# counterMeter.net
KiCad netlist of a schematic drawn in EAGLE
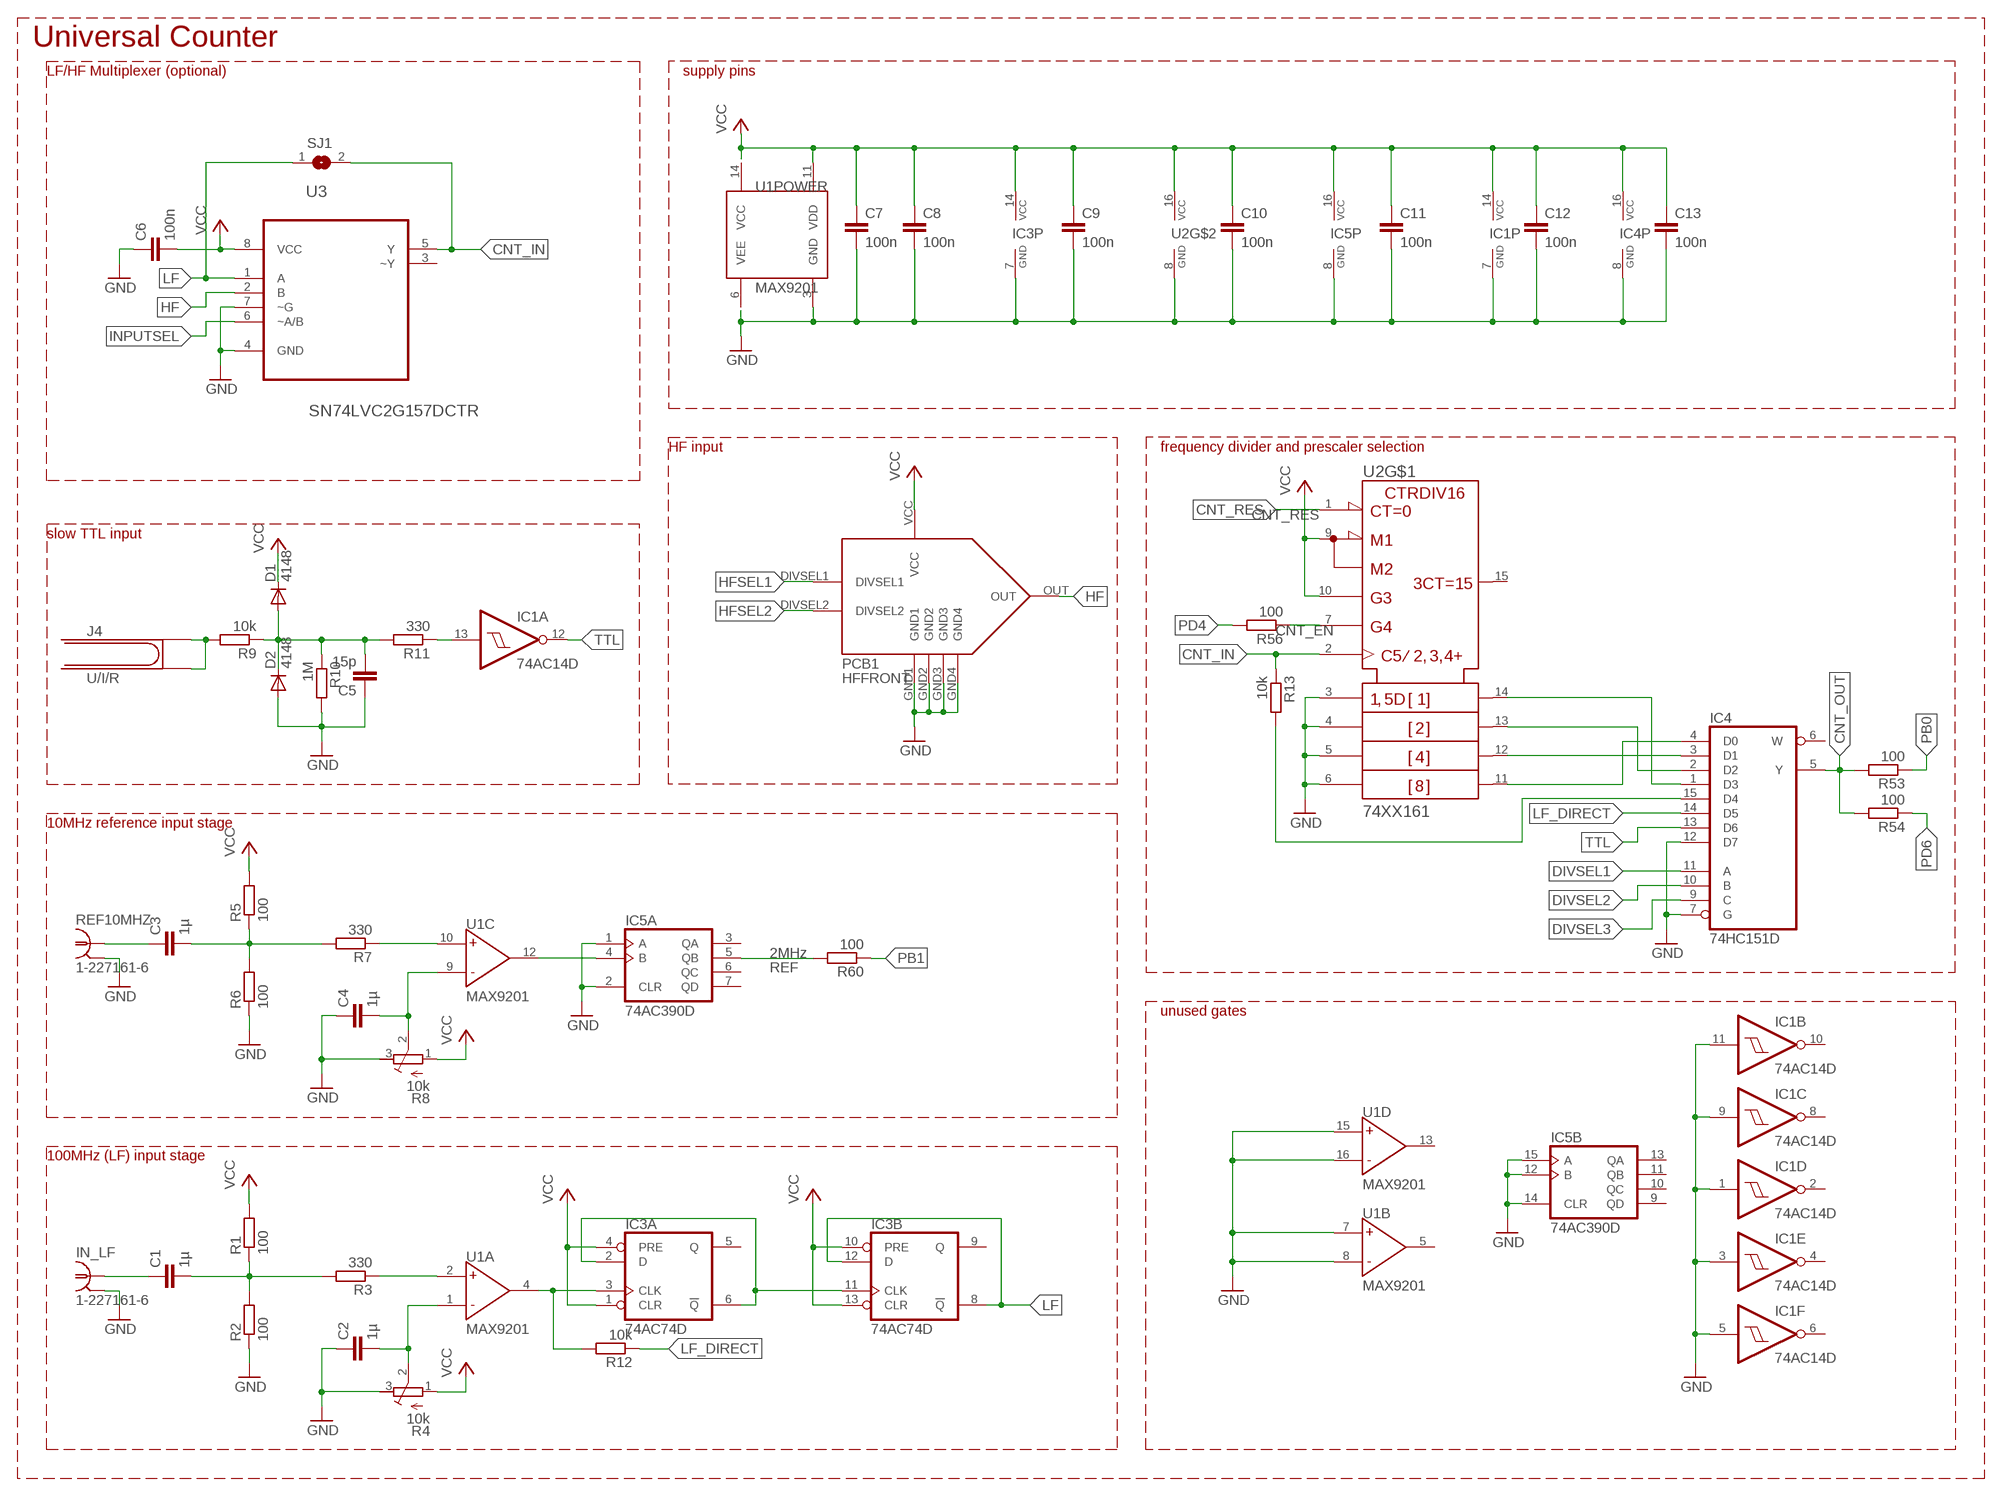
[diagram p0: schematic, sheet 1, part 1 of 2]
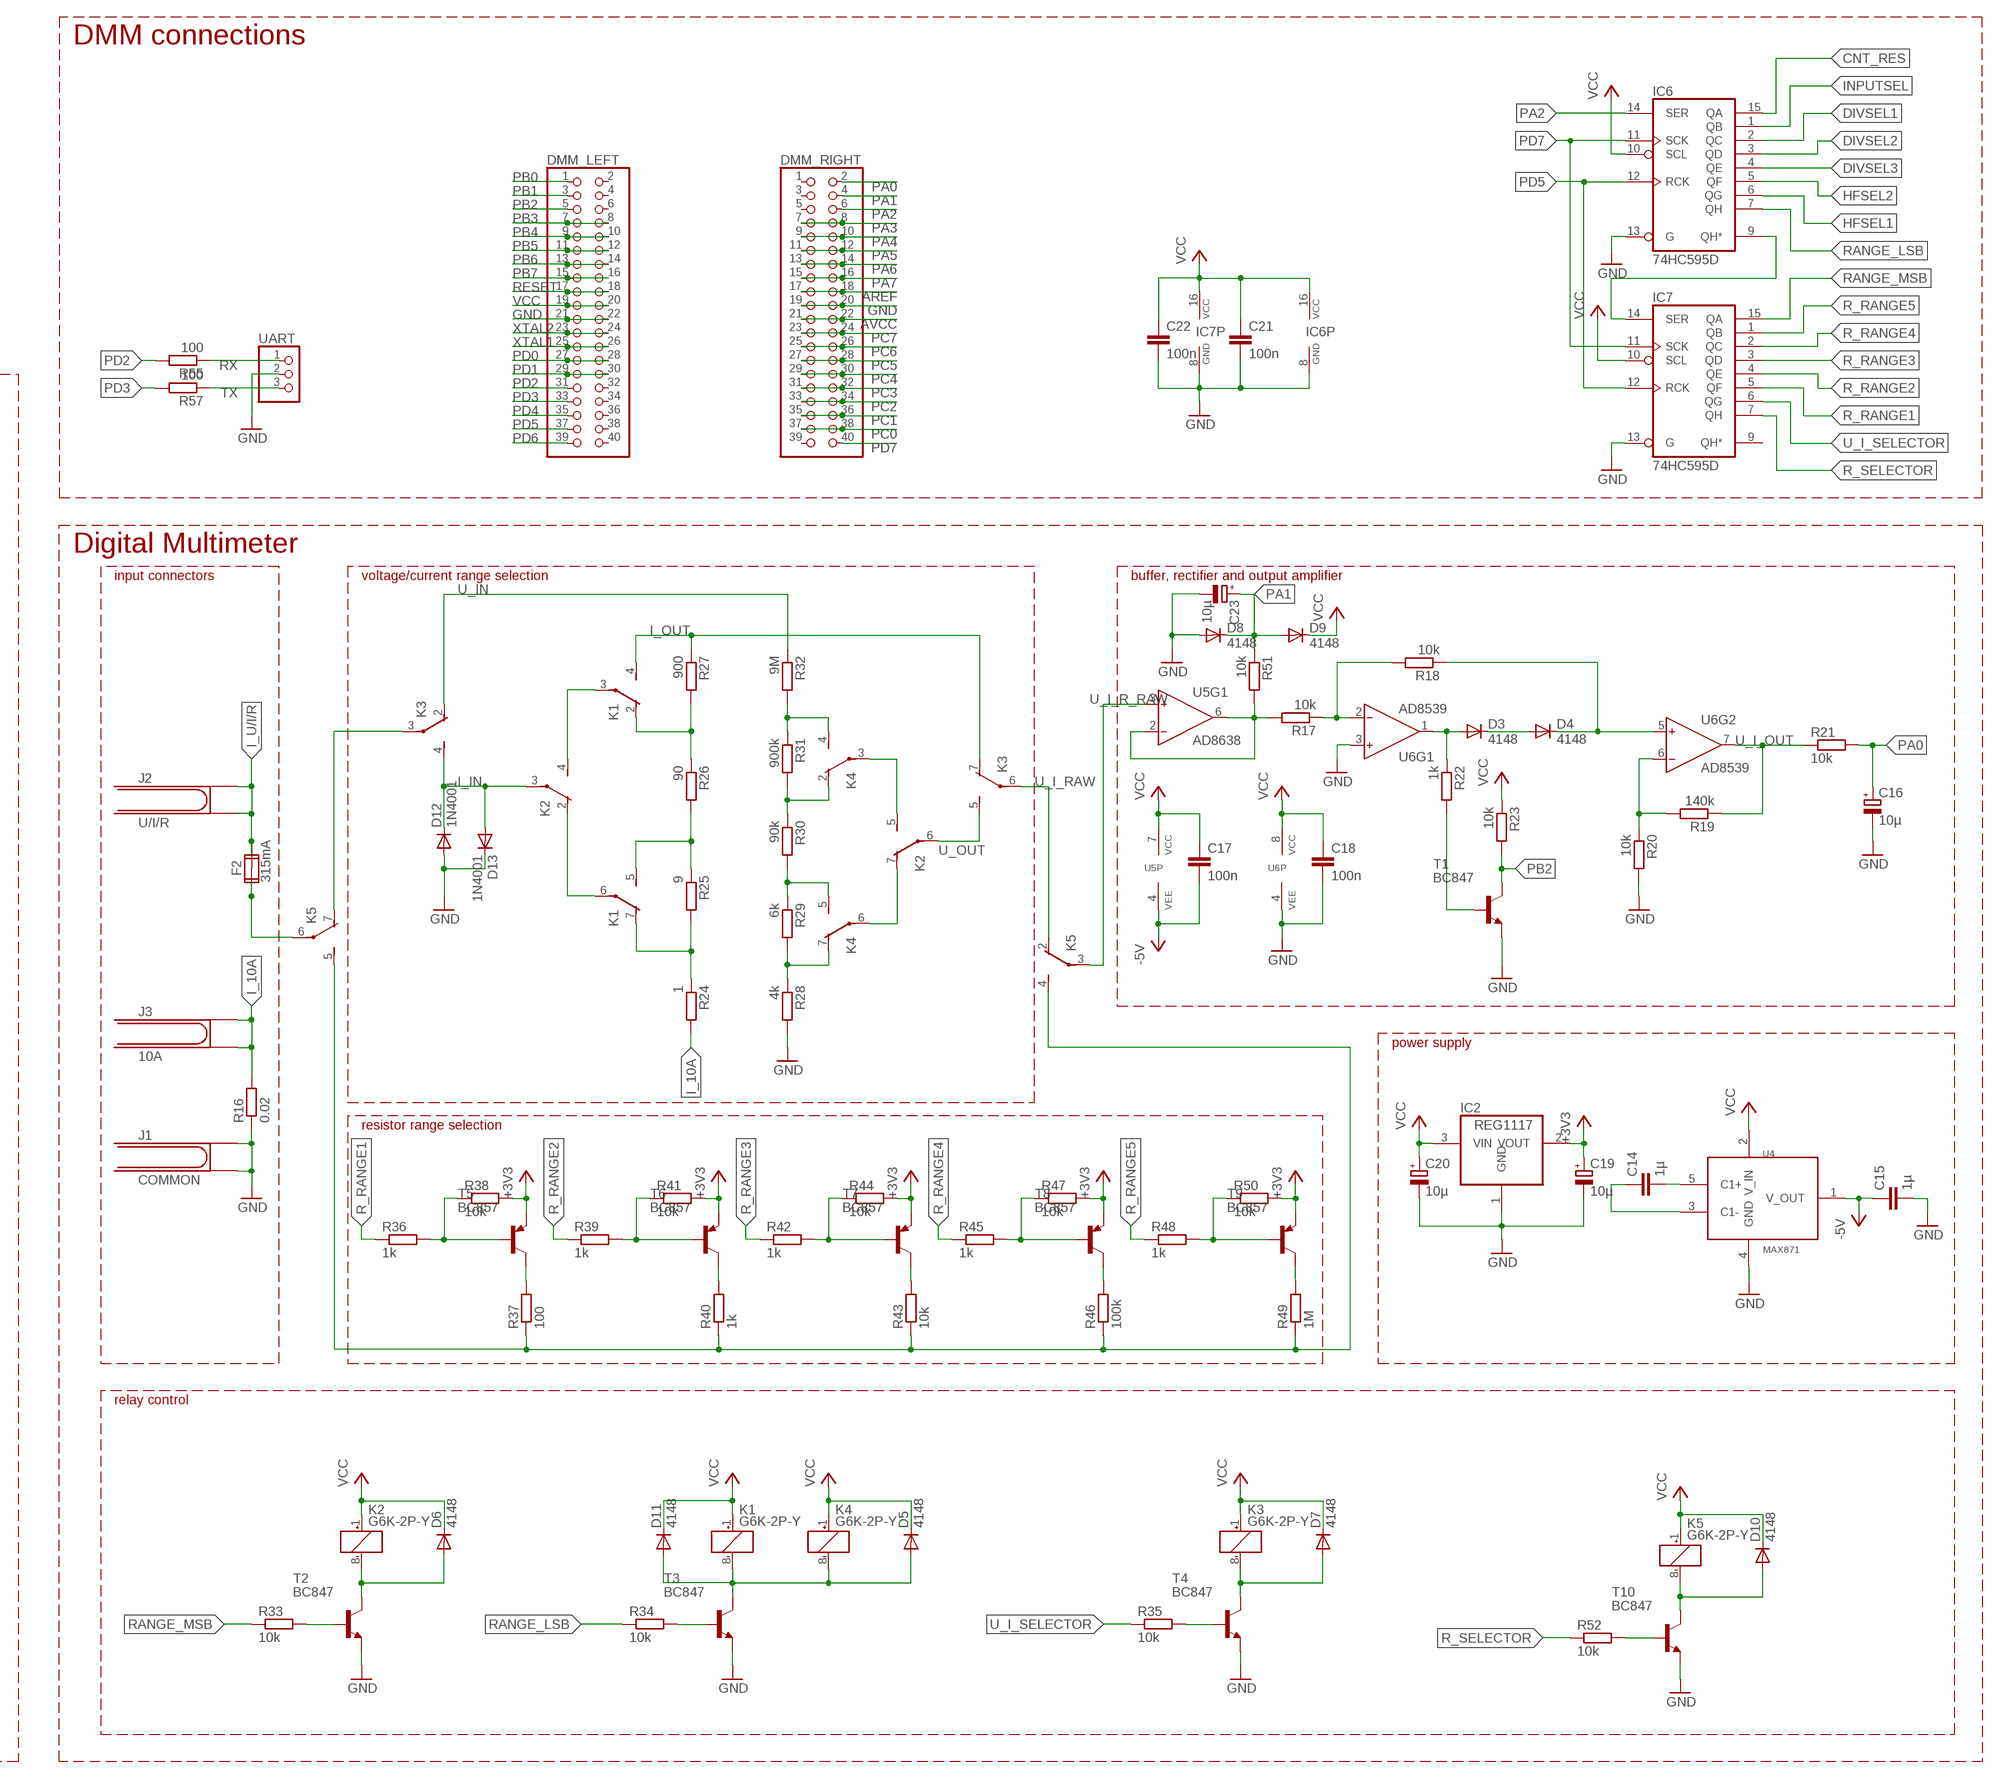
[diagram p1: schematic, sheet 1, part 2 of 2]

(export (version "E")
  (design (tool "Eeschema 10.0.6"))
  (components
    (comp (ref "C1")
      (value "1µ")
      (footprint "eagle-import:C0603")
      (libsource (lib "eagle-import") (part "C-EUC0603"))
    )
    (comp (ref "C2")
      (value "1µ")
      (footprint "eagle-import:C0603")
      (libsource (lib "eagle-import") (part "C-EUC0603"))
    )
    (comp (ref "C3")
      (value "1µ")
      (footprint "eagle-import:C0603")
      (libsource (lib "eagle-import") (part "C-EUC0603"))
    )
    (comp (ref "C4")
      (value "1µ")
      (footprint "eagle-import:C0603")
      (libsource (lib "eagle-import") (part "C-EUC0603"))
    )
    (comp (ref "C5")
      (value "15p")
      (footprint "eagle-import:C0603")
      (libsource (lib "eagle-import") (part "C-EUC0603"))
    )
    (comp (ref "C6")
      (value "100n")
      (footprint "eagle-import:C0603")
      (libsource (lib "eagle-import") (part "C-EUC0603"))
    )
    (comp (ref "C7")
      (value "100n")
      (footprint "eagle-import:C0603")
      (libsource (lib "eagle-import") (part "C-EUC0603"))
    )
    (comp (ref "C8")
      (value "100n")
      (footprint "eagle-import:C0603")
      (libsource (lib "eagle-import") (part "C-EUC0603"))
    )
    (comp (ref "C9")
      (value "100n")
      (footprint "eagle-import:C0603")
      (libsource (lib "eagle-import") (part "C-EUC0603"))
    )
    (comp (ref "C10")
      (value "100n")
      (footprint "eagle-import:C0603")
      (libsource (lib "eagle-import") (part "C-EUC0603"))
    )
    (comp (ref "C11")
      (value "100n")
      (footprint "eagle-import:C0603")
      (libsource (lib "eagle-import") (part "C-EUC0603"))
    )
    (comp (ref "C12")
      (value "100n")
      (footprint "eagle-import:C0603")
      (libsource (lib "eagle-import") (part "C-EUC0603"))
    )
    (comp (ref "C13")
      (value "100n")
      (footprint "eagle-import:C0603")
      (libsource (lib "eagle-import") (part "C-EUC0603"))
    )
    (comp (ref "C14")
      (value "1µ")
      (footprint "eagle-import:C0603")
      (libsource (lib "eagle-import") (part "C-EUC0603"))
    )
    (comp (ref "C15")
      (value "1µ")
      (footprint "eagle-import:C0603")
      (libsource (lib "eagle-import") (part "C-EUC0603"))
    )
    (comp (ref "C16")
      (value "10µ")
      (footprint "eagle-import:E2-5")
      (libsource (lib "eagle-import") (part "CPOL-EUE2-5"))
    )
    (comp (ref "C17")
      (value "100n")
      (footprint "eagle-import:C0603")
      (libsource (lib "eagle-import") (part "C-EUC0603"))
    )
    (comp (ref "C18")
      (value "100n")
      (footprint "eagle-import:C0603")
      (libsource (lib "eagle-import") (part "C-EUC0603"))
    )
    (comp (ref "C19")
      (value "10µ")
      (footprint "eagle-import:E2-5")
      (libsource (lib "eagle-import") (part "CPOL-EUE2-5"))
    )
    (comp (ref "C20")
      (value "10µ")
      (footprint "eagle-import:E2-5")
      (libsource (lib "eagle-import") (part "CPOL-EUE2-5"))
    )
    (comp (ref "C21")
      (value "100n")
      (footprint "eagle-import:C0603")
      (libsource (lib "eagle-import") (part "C-EUC0603"))
    )
    (comp (ref "C22")
      (value "100n")
      (footprint "eagle-import:C0603")
      (libsource (lib "eagle-import") (part "C-EUC0603"))
    )
    (comp (ref "C23")
      (value "10µ")
      (footprint "eagle-import:E2-5")
      (libsource (lib "eagle-import") (part "CPOL-EUE2-5"))
    )
    (comp (ref "D1")
      (value "4148")
      (footprint "eagle-import:SOD323-W")
      (libsource (lib "eagle-import") (part "DIODE-SOD323-W"))
    )
    (comp (ref "D2")
      (value "4148")
      (footprint "eagle-import:SOD323-W")
      (libsource (lib "eagle-import") (part "DIODE-SOD323-W"))
    )
    (comp (ref "D3")
      (value "4148")
      (footprint "eagle-import:SOD323-W")
      (libsource (lib "eagle-import") (part "DIODE-SOD323-W"))
    )
    (comp (ref "D4")
      (value "4148")
      (footprint "eagle-import:SOD323-W")
      (libsource (lib "eagle-import") (part "DIODE-SOD323-W"))
    )
    (comp (ref "D5")
      (value "4148")
      (footprint "eagle-import:SOD323-W")
      (libsource (lib "eagle-import") (part "DIODE-SOD323-W"))
    )
    (comp (ref "D6")
      (value "4148")
      (footprint "eagle-import:SOD323-W")
      (libsource (lib "eagle-import") (part "DIODE-SOD323-W"))
    )
    (comp (ref "D7")
      (value "4148")
      (footprint "eagle-import:SOD323-W")
      (libsource (lib "eagle-import") (part "DIODE-SOD323-W"))
    )
    (comp (ref "D8")
      (value "4148")
      (footprint "eagle-import:SOD323-W")
      (libsource (lib "eagle-import") (part "DIODE-SOD323-W"))
    )
    (comp (ref "D9")
      (value "4148")
      (footprint "eagle-import:SOD323-W")
      (libsource (lib "eagle-import") (part "DIODE-SOD323-W"))
    )
    (comp (ref "D10")
      (value "4148")
      (footprint "eagle-import:SOD323-W")
      (libsource (lib "eagle-import") (part "DIODE-SOD323-W"))
    )
    (comp (ref "D11")
      (value "4148")
      (footprint "eagle-import:SOD323-W")
      (libsource (lib "eagle-import") (part "DIODE-SOD323-W"))
    )
    (comp (ref "D12")
      (value "1N4001")
      (footprint "eagle-import:DO41-10")
      (libsource (lib "eagle-import") (part "1N4004"))
    )
    (comp (ref "D13")
      (value "1N4001")
      (footprint "eagle-import:DO41-10")
      (libsource (lib "eagle-import") (part "1N4004"))
    )
    (comp (ref "DMM_LEFT")
      (value "PINHD-2X20")
      (footprint "eagle-import:2X20")
      (libsource (lib "eagle-import") (part "PINHD-2X20"))
    )
    (comp (ref "DMM_RIGHT")
      (value "PINHD-2X20")
      (footprint "eagle-import:2X20")
      (libsource (lib "eagle-import") (part "PINHD-2X20"))
    )
    (comp (ref "F2")
      (value "315mA")
      (footprint "eagle-import:FUSE1")
      (libsource (lib "eagle-import") (part "FUSE2P"))
    )
    (comp (ref "IC1")
      (value "74AC14D")
      (footprint "eagle-import:SO14")
      (libsource (lib "eagle-import") (part "7414DAC"))
    )
    (comp (ref "IC2")
      (value "REG1117")
      (footprint "eagle-import:SOT223")
      (libsource (lib "eagle-import") (part "REG1117"))
    )
    (comp (ref "IC3")
      (value "74AC74D")
      (footprint "eagle-import:SO14")
      (libsource (lib "eagle-import") (part "7474DAC"))
    )
    (comp (ref "IC4")
      (value "74HC151D")
      (footprint "eagle-import:SO16")
      (libsource (lib "eagle-import") (part "74151DHC"))
    )
    (comp (ref "IC5")
      (value "74AC390D")
      (footprint "eagle-import:SO16")
      (libsource (lib "eagle-import") (part "74390DAC"))
    )
    (comp (ref "IC6")
      (value "74HC595D")
      (footprint "eagle-import:SO16")
      (libsource (lib "eagle-import") (part "74595DHC"))
    )
    (comp (ref "IC7")
      (value "74HC595D")
      (footprint "eagle-import:SO16")
      (libsource (lib "eagle-import") (part "74595DHC"))
    )
    (comp (ref "IN_LF")
      (value "1-227161-6")
      (footprint "eagle-import:AMP_227161")
      (fields (field (name "MF") "TYCO ELECTRONICS"))
      (libsource (lib "eagle-import") (part "?2271611--6"))
    )
    (comp (ref "J1")
      (value "COMMON")
      (footprint "eagle-import:4MMJACK")
      (libsource (lib "eagle-import") (part "4MMJACK"))
    )
    (comp (ref "J2")
      (value "U/I/R")
      (footprint "eagle-import:4MMJACK")
      (libsource (lib "eagle-import") (part "4MMJACK"))
    )
    (comp (ref "J3")
      (value "10A")
      (footprint "eagle-import:4MMJACK")
      (libsource (lib "eagle-import") (part "4MMJACK"))
    )
    (comp (ref "J4")
      (value "U/I/R")
      (footprint "eagle-import:4MMJACK")
      (libsource (lib "eagle-import") (part "4MMJACK"))
    )
    (comp (ref "K1")
      (value "G6K-2P-Y")
      (footprint "eagle-import:G6K-2P-Y")
      (fields (field (name "MF") "OMRON COMPONENTS USA") (field (name "MPN") "G6K-2P-Y DC12"))
      (libsource (lib "eagle-import") (part "G6K-2P-Y"))
    )
    (comp (ref "K2")
      (value "G6K-2P-Y")
      (footprint "eagle-import:G6K-2P-Y")
      (fields (field (name "MF") "OMRON COMPONENTS USA") (field (name "MPN") "G6K-2P-Y DC12"))
      (libsource (lib "eagle-import") (part "G6K-2P-Y"))
    )
    (comp (ref "K3")
      (value "G6K-2P-Y")
      (footprint "eagle-import:G6K-2P-Y")
      (fields (field (name "MF") "OMRON COMPONENTS USA") (field (name "MPN") "G6K-2P-Y DC12"))
      (libsource (lib "eagle-import") (part "G6K-2P-Y"))
    )
    (comp (ref "K4")
      (value "G6K-2P-Y")
      (footprint "eagle-import:G6K-2P-Y")
      (fields (field (name "MF") "OMRON COMPONENTS USA") (field (name "MPN") "G6K-2P-Y DC12"))
      (libsource (lib "eagle-import") (part "G6K-2P-Y"))
    )
    (comp (ref "K5")
      (value "G6K-2P-Y")
      (footprint "eagle-import:G6K-2P-Y")
      (fields (field (name "MF") "OMRON COMPONENTS USA") (field (name "MPN") "G6K-2P-Y DC12"))
      (libsource (lib "eagle-import") (part "G6K-2P-Y"))
    )
    (comp (ref "PCB1")
      (value "HFFRONT")
      (footprint "eagle-import:HFFRONT")
      (libsource (lib "eagle-import") (part "HFFRONT"))
    )
    (comp (ref "R1")
      (value "100")
      (footprint "eagle-import:R0603")
      (libsource (lib "eagle-import") (part "R-EU_R0603"))
    )
    (comp (ref "R2")
      (value "100")
      (footprint "eagle-import:R0603")
      (libsource (lib "eagle-import") (part "R-EU_R0603"))
    )
    (comp (ref "R3")
      (value "330")
      (footprint "eagle-import:R0603")
      (libsource (lib "eagle-import") (part "R-EU_R0603"))
    )
    (comp (ref "R4")
      (value "10k")
      (footprint "eagle-import:RTRIM64W")
      (libsource (lib "eagle-import") (part "R-TRIMM64W"))
    )
    (comp (ref "R5")
      (value "100")
      (footprint "eagle-import:R0603")
      (libsource (lib "eagle-import") (part "R-EU_R0603"))
    )
    (comp (ref "R6")
      (value "100")
      (footprint "eagle-import:R0603")
      (libsource (lib "eagle-import") (part "R-EU_R0603"))
    )
    (comp (ref "R7")
      (value "330")
      (footprint "eagle-import:R0603")
      (libsource (lib "eagle-import") (part "R-EU_R0603"))
    )
    (comp (ref "R8")
      (value "10k")
      (footprint "eagle-import:RTRIM64W")
      (libsource (lib "eagle-import") (part "R-TRIMM64W"))
    )
    (comp (ref "R9")
      (value "10k")
      (footprint "eagle-import:R0603")
      (libsource (lib "eagle-import") (part "R-EU_R0603"))
    )
    (comp (ref "R10")
      (value "1M")
      (footprint "eagle-import:R0603")
      (libsource (lib "eagle-import") (part "R-EU_R0603"))
    )
    (comp (ref "R11")
      (value "330")
      (footprint "eagle-import:R0603")
      (libsource (lib "eagle-import") (part "R-EU_R0603"))
    )
    (comp (ref "R12")
      (value "10k")
      (footprint "eagle-import:R0603")
      (libsource (lib "eagle-import") (part "R-EU_R0603"))
    )
    (comp (ref "R13")
      (value "10k")
      (footprint "eagle-import:R0603")
      (libsource (lib "eagle-import") (part "R-EU_R0603"))
    )
    (comp (ref "R16")
      (value "0.02")
      (footprint "eagle-import:R2512")
      (libsource (lib "eagle-import") (part "R-EU_R2512"))
    )
    (comp (ref "R17")
      (value "10k")
      (footprint "eagle-import:R0603")
      (libsource (lib "eagle-import") (part "R-EU_R0603"))
    )
    (comp (ref "R18")
      (value "10k")
      (footprint "eagle-import:R0603")
      (libsource (lib "eagle-import") (part "R-EU_R0603"))
    )
    (comp (ref "R19")
      (value "140k")
      (footprint "eagle-import:R0603")
      (libsource (lib "eagle-import") (part "R-EU_R0603"))
    )
    (comp (ref "R20")
      (value "10k")
      (footprint "eagle-import:R0603")
      (libsource (lib "eagle-import") (part "R-EU_R0603"))
    )
    (comp (ref "R21")
      (value "10k")
      (footprint "eagle-import:R0603")
      (libsource (lib "eagle-import") (part "R-EU_R0603"))
    )
    (comp (ref "R22")
      (value "1k")
      (footprint "eagle-import:R0603")
      (libsource (lib "eagle-import") (part "R-EU_R0603"))
    )
    (comp (ref "R23")
      (value "10k")
      (footprint "eagle-import:R0603")
      (libsource (lib "eagle-import") (part "R-EU_R0603"))
    )
    (comp (ref "R24")
      (value "1")
      (footprint "eagle-import:R0603")
      (libsource (lib "eagle-import") (part "R-EU_R0603"))
    )
    (comp (ref "R25")
      (value "9")
      (footprint "eagle-import:R0603")
      (libsource (lib "eagle-import") (part "R-EU_R0603"))
    )
    (comp (ref "R26")
      (value "90")
      (footprint "eagle-import:R0603")
      (libsource (lib "eagle-import") (part "R-EU_R0603"))
    )
    (comp (ref "R27")
      (value "900")
      (footprint "eagle-import:R0603")
      (libsource (lib "eagle-import") (part "R-EU_R0603"))
    )
    (comp (ref "R28")
      (value "4k")
      (footprint "eagle-import:R0603")
      (libsource (lib "eagle-import") (part "R-EU_R0603"))
    )
    (comp (ref "R29")
      (value "6k")
      (footprint "eagle-import:R0603")
      (libsource (lib "eagle-import") (part "R-EU_R0603"))
    )
    (comp (ref "R30")
      (value "90k")
      (footprint "eagle-import:R0603")
      (libsource (lib "eagle-import") (part "R-EU_R0603"))
    )
    (comp (ref "R31")
      (value "900k")
      (footprint "eagle-import:R0603")
      (libsource (lib "eagle-import") (part "R-EU_R0603"))
    )
    (comp (ref "R32")
      (value "9M")
      (footprint "eagle-import:R0603")
      (libsource (lib "eagle-import") (part "R-EU_R0603"))
    )
    (comp (ref "R33")
      (value "10k")
      (footprint "eagle-import:R0603")
      (libsource (lib "eagle-import") (part "R-EU_R0603"))
    )
    (comp (ref "R34")
      (value "10k")
      (footprint "eagle-import:R0603")
      (libsource (lib "eagle-import") (part "R-EU_R0603"))
    )
    (comp (ref "R35")
      (value "10k")
      (footprint "eagle-import:R0603")
      (libsource (lib "eagle-import") (part "R-EU_R0603"))
    )
    (comp (ref "R36")
      (value "1k")
      (footprint "eagle-import:R0603")
      (libsource (lib "eagle-import") (part "R-EU_R0603"))
    )
    (comp (ref "R37")
      (value "100")
      (footprint "eagle-import:R0603")
      (libsource (lib "eagle-import") (part "R-EU_R0603"))
    )
    (comp (ref "R38")
      (value "10k")
      (footprint "eagle-import:R0603")
      (libsource (lib "eagle-import") (part "R-EU_R0603"))
    )
    (comp (ref "R39")
      (value "1k")
      (footprint "eagle-import:R0603")
      (libsource (lib "eagle-import") (part "R-EU_R0603"))
    )
    (comp (ref "R40")
      (value "1k")
      (footprint "eagle-import:R0603")
      (libsource (lib "eagle-import") (part "R-EU_R0603"))
    )
    (comp (ref "R41")
      (value "10k")
      (footprint "eagle-import:R0603")
      (libsource (lib "eagle-import") (part "R-EU_R0603"))
    )
    (comp (ref "R42")
      (value "1k")
      (footprint "eagle-import:R0603")
      (libsource (lib "eagle-import") (part "R-EU_R0603"))
    )
    (comp (ref "R43")
      (value "10k")
      (footprint "eagle-import:R0603")
      (libsource (lib "eagle-import") (part "R-EU_R0603"))
    )
    (comp (ref "R44")
      (value "10k")
      (footprint "eagle-import:R0603")
      (libsource (lib "eagle-import") (part "R-EU_R0603"))
    )
    (comp (ref "R45")
      (value "1k")
      (footprint "eagle-import:R0603")
      (libsource (lib "eagle-import") (part "R-EU_R0603"))
    )
    (comp (ref "R46")
      (value "100k")
      (footprint "eagle-import:R0603")
      (libsource (lib "eagle-import") (part "R-EU_R0603"))
    )
    (comp (ref "R47")
      (value "10k")
      (footprint "eagle-import:R0603")
      (libsource (lib "eagle-import") (part "R-EU_R0603"))
    )
    (comp (ref "R48")
      (value "1k")
      (footprint "eagle-import:R0603")
      (libsource (lib "eagle-import") (part "R-EU_R0603"))
    )
    (comp (ref "R49")
      (value "1M")
      (footprint "eagle-import:R0603")
      (libsource (lib "eagle-import") (part "R-EU_R0603"))
    )
    (comp (ref "R50")
      (value "10k")
      (footprint "eagle-import:R0603")
      (libsource (lib "eagle-import") (part "R-EU_R0603"))
    )
    (comp (ref "R51")
      (value "10k")
      (footprint "eagle-import:R0603")
      (libsource (lib "eagle-import") (part "R-EU_R0603"))
    )
    (comp (ref "R52")
      (value "10k")
      (footprint "eagle-import:R0603")
      (libsource (lib "eagle-import") (part "R-EU_R0603"))
    )
    (comp (ref "R53")
      (value "100")
      (footprint "eagle-import:R0603")
      (libsource (lib "eagle-import") (part "R-EU_R0603"))
    )
    (comp (ref "R54")
      (value "100")
      (footprint "eagle-import:R0603")
      (libsource (lib "eagle-import") (part "R-EU_R0603"))
    )
    (comp (ref "R55")
      (value "100")
      (footprint "eagle-import:R0603")
      (libsource (lib "eagle-import") (part "R-EU_R0603"))
    )
    (comp (ref "R56")
      (value "100")
      (footprint "eagle-import:R0603")
      (libsource (lib "eagle-import") (part "R-EU_R0603"))
    )
    (comp (ref "R57")
      (value "100")
      (footprint "eagle-import:R0603")
      (libsource (lib "eagle-import") (part "R-EU_R0603"))
    )
    (comp (ref "R60")
      (value "100")
      (footprint "eagle-import:R0603")
      (libsource (lib "eagle-import") (part "R-EU_R0603"))
    )
    (comp (ref "REF10MHZ")
      (value "1-227161-6")
      (footprint "eagle-import:AMP_227161")
      (fields (field (name "MF") "TYCO ELECTRONICS"))
      (libsource (lib "eagle-import") (part "?2271611--6"))
    )
    (comp (ref "SJ1") (value "SJ") (footprint "eagle-import:SJ") (libsource (lib "eagle-import") (part "SJ")))
    (comp (ref "T1")
      (value "BC847")
      (footprint "eagle-import:SOT23")
      (libsource (lib "eagle-import") (part "BC847"))
    )
    (comp (ref "T2")
      (value "BC847")
      (footprint "eagle-import:SOT23")
      (libsource (lib "eagle-import") (part "BC847"))
    )
    (comp (ref "T3")
      (value "BC847")
      (footprint "eagle-import:SOT23")
      (libsource (lib "eagle-import") (part "BC847"))
    )
    (comp (ref "T4")
      (value "BC847")
      (footprint "eagle-import:SOT23")
      (libsource (lib "eagle-import") (part "BC847"))
    )
    (comp (ref "T5")
      (value "BC857")
      (footprint "eagle-import:SOT23-BEC")
      (libsource (lib "eagle-import") (part "-PNP-SOT23-BECBC857C"))
    )
    (comp (ref "T6")
      (value "BC857")
      (footprint "eagle-import:SOT23-BEC")
      (libsource (lib "eagle-import") (part "-PNP-SOT23-BECBC857C"))
    )
    (comp (ref "T7")
      (value "BC857")
      (footprint "eagle-import:SOT23-BEC")
      (libsource (lib "eagle-import") (part "-PNP-SOT23-BECBC857C"))
    )
    (comp (ref "T8")
      (value "BC857")
      (footprint "eagle-import:SOT23-BEC")
      (libsource (lib "eagle-import") (part "-PNP-SOT23-BECBC857C"))
    )
    (comp (ref "T9")
      (value "BC857")
      (footprint "eagle-import:SOT23-BEC")
      (libsource (lib "eagle-import") (part "-PNP-SOT23-BECBC857C"))
    )
    (comp (ref "T10")
      (value "BC847")
      (footprint "eagle-import:SOT23")
      (libsource (lib "eagle-import") (part "BC847"))
    )
    (comp (ref "U1")
      (value "MAX9201")
      (footprint "eagle-import:SOIC16")
      (libsource (lib "eagle-import") (part "MAX9201"))
    )
    (comp (ref "U2")
      (value "74XX161")
      (footprint "eagle-import:SOIC16")
      (libsource (lib "eagle-import") (part "74XX161"))
    )
    (comp (ref "U3")
      (value "SN74LVC2G157DCTR")
      (footprint "eagle-import:SOP65P400X130-8N")
      (libsource (lib "eagle-import") (part "SN74LVC2G157DCTR"))
    )
    (comp (ref "U4")
      (value "MAX871")
      (footprint "eagle-import:SOT23-5")
      (libsource (lib "eagle-import") (part "MAX871"))
    )
    (comp (ref "U5")
      (value "AD8638")
      (footprint "eagle-import:SOIC8")
      (libsource (lib "eagle-import") (part "AD8638"))
    )
    (comp (ref "U6")
      (value "AD8539")
      (footprint "eagle-import:SOIC8")
      (libsource (lib "eagle-import") (part "AD8539"))
    )
    (comp (ref "UART")
      (value "PINHD-1X3")
      (footprint "eagle-import:1X03")
      (libsource (lib "eagle-import") (part "PINHD-1X3"))
    )
  )
  (nets
    (net (code "1") (name "+3V3") (class "Default")
      (node (ref "C19") (pin "+") (pinfunction "+_+") (pintype "passive"))
      (node (ref "IC2") (pin "2") (pinfunction "VOUT_2") (pintype "output"))
      (node (ref "R38") (pin "2") (pinfunction "2_2") (pintype "passive"))
      (node (ref "R41") (pin "2") (pinfunction "2_2") (pintype "passive"))
      (node (ref "R44") (pin "2") (pinfunction "2_2") (pintype "passive"))
      (node (ref "R47") (pin "2") (pinfunction "2_2") (pintype "passive"))
      (node (ref "R50") (pin "2") (pinfunction "2_2") (pintype "passive"))
      (node (ref "T5") (pin "E") (pinfunction "E_E") (pintype "passive"))
      (node (ref "T6") (pin "E") (pinfunction "E_E") (pintype "passive"))
      (node (ref "T7") (pin "E") (pinfunction "E_E") (pintype "passive"))
      (node (ref "T8") (pin "E") (pinfunction "E_E") (pintype "passive"))
      (node (ref "T9") (pin "E") (pinfunction "E_E") (pintype "passive"))
    )
    (net (code "2") (name "-5V") (class "Default")
      (node (ref "C15") (pin "1") (pinfunction "1_1") (pintype "passive"))
      (node (ref "C17") (pin "2") (pinfunction "2_2") (pintype "passive"))
      (node (ref "U4") (pin "1") (pinfunction "V_OUT_1") (pintype "bidirectional"))
      (node (ref "U5") (pin "4") (pinfunction "VEE_4") (pintype "bidirectional"))
    )
    (net (code "3") (name "/AREF") (class "Default")
      (node (ref "DMM_RIGHT") (pin "17") (pinfunction "17_17") (pintype "passive"))
      (node (ref "DMM_RIGHT") (pin "18") (pinfunction "18_18") (pintype "passive"))
    )
    (net (code "4") (name "/AVCC") (class "Default")
      (node (ref "DMM_RIGHT") (pin "21") (pinfunction "21_21") (pintype "passive"))
      (node (ref "DMM_RIGHT") (pin "22") (pinfunction "22_22") (pintype "passive"))
    )
    (net (code "5") (name "/CNT_EN") (class "Default")
      (node (ref "R56") (pin "1") (pinfunction "1_1") (pintype "passive"))
      (node (ref "U2") (pin "7") (pinfunction "ENP_7") (pintype "input"))
    )
    (net (code "6") (name "/I_IN") (class "Default")
      (node (ref "D12") (pin "C") (pinfunction "C_C") (pintype "passive"))
      (node (ref "D13") (pin "A") (pinfunction "A_A") (pintype "passive"))
      (node (ref "K2") (pin "3") (pinfunction "P_3") (pintype "passive"))
      (node (ref "K3") (pin "4") (pinfunction "S_4") (pintype "passive"))
    )
    (net (code "7") (name "/I_OUT") (class "Default")
      (node (ref "K1") (pin "4") (pinfunction "S_4") (pintype "passive"))
      (node (ref "K3") (pin "7") (pinfunction "O_7") (pintype "passive"))
      (node (ref "R27") (pin "1") (pinfunction "1_1") (pintype "passive"))
    )
    (net (code "8") (name "/PA3") (class "Default")
      (node (ref "DMM_RIGHT") (pin "7") (pinfunction "7_7") (pintype "passive"))
      (node (ref "DMM_RIGHT") (pin "8") (pinfunction "8_8") (pintype "passive"))
    )
    (net (code "9") (name "/PA4") (class "Default")
      (node (ref "DMM_RIGHT") (pin "10") (pinfunction "10_10") (pintype "passive"))
      (node (ref "DMM_RIGHT") (pin "9") (pinfunction "9_9") (pintype "passive"))
    )
    (net (code "10") (name "/PA5") (class "Default")
      (node (ref "DMM_RIGHT") (pin "11") (pinfunction "11_11") (pintype "passive"))
      (node (ref "DMM_RIGHT") (pin "12") (pinfunction "12_12") (pintype "passive"))
    )
    (net (code "11") (name "/PA6") (class "Default")
      (node (ref "DMM_RIGHT") (pin "13") (pinfunction "13_13") (pintype "passive"))
      (node (ref "DMM_RIGHT") (pin "14") (pinfunction "14_14") (pintype "passive"))
    )
    (net (code "12") (name "/PA7") (class "Default")
      (node (ref "DMM_RIGHT") (pin "15") (pinfunction "15_15") (pintype "passive"))
      (node (ref "DMM_RIGHT") (pin "16") (pinfunction "16_16") (pintype "passive"))
    )
    (net (code "13") (name "/PB3") (class "Default")
      (node (ref "DMM_LEFT") (pin "7") (pinfunction "7_7") (pintype "passive"))
      (node (ref "DMM_LEFT") (pin "8") (pinfunction "8_8") (pintype "passive"))
    )
    (net (code "14") (name "/PB4") (class "Default")
      (node (ref "DMM_LEFT") (pin "10") (pinfunction "10_10") (pintype "passive"))
      (node (ref "DMM_LEFT") (pin "9") (pinfunction "9_9") (pintype "passive"))
    )
    (net (code "15") (name "/PB5") (class "Default")
      (node (ref "DMM_LEFT") (pin "11") (pinfunction "11_11") (pintype "passive"))
      (node (ref "DMM_LEFT") (pin "12") (pinfunction "12_12") (pintype "passive"))
    )
    (net (code "16") (name "/PB6") (class "Default")
      (node (ref "DMM_LEFT") (pin "13") (pinfunction "13_13") (pintype "passive"))
      (node (ref "DMM_LEFT") (pin "14") (pinfunction "14_14") (pintype "passive"))
    )
    (net (code "17") (name "/PB7") (class "Default")
      (node (ref "DMM_LEFT") (pin "15") (pinfunction "15_15") (pintype "passive"))
      (node (ref "DMM_LEFT") (pin "16") (pinfunction "16_16") (pintype "passive"))
    )
    (net (code "18") (name "/PC0") (class "Default")
      (node (ref "DMM_RIGHT") (pin "37") (pinfunction "37_37") (pintype "passive"))
      (node (ref "DMM_RIGHT") (pin "38") (pinfunction "38_38") (pintype "passive"))
    )
    (net (code "19") (name "/PC1") (class "Default")
      (node (ref "DMM_RIGHT") (pin "35") (pinfunction "35_35") (pintype "passive"))
      (node (ref "DMM_RIGHT") (pin "36") (pinfunction "36_36") (pintype "passive"))
    )
    (net (code "20") (name "/PC2") (class "Default")
      (node (ref "DMM_RIGHT") (pin "33") (pinfunction "33_33") (pintype "passive"))
      (node (ref "DMM_RIGHT") (pin "34") (pinfunction "34_34") (pintype "passive"))
    )
    (net (code "21") (name "/PC3") (class "Default")
      (node (ref "DMM_RIGHT") (pin "31") (pinfunction "31_31") (pintype "passive"))
      (node (ref "DMM_RIGHT") (pin "32") (pinfunction "32_32") (pintype "passive"))
    )
    (net (code "22") (name "/PC4") (class "Default")
      (node (ref "DMM_RIGHT") (pin "29") (pinfunction "29_29") (pintype "passive"))
      (node (ref "DMM_RIGHT") (pin "30") (pinfunction "30_30") (pintype "passive"))
    )
    (net (code "23") (name "/PC5") (class "Default")
      (node (ref "DMM_RIGHT") (pin "27") (pinfunction "27_27") (pintype "passive"))
      (node (ref "DMM_RIGHT") (pin "28") (pinfunction "28_28") (pintype "passive"))
    )
    (net (code "24") (name "/PC6") (class "Default")
      (node (ref "DMM_RIGHT") (pin "25") (pinfunction "25_25") (pintype "passive"))
      (node (ref "DMM_RIGHT") (pin "26") (pinfunction "26_26") (pintype "passive"))
    )
    (net (code "25") (name "/PC7") (class "Default")
      (node (ref "DMM_RIGHT") (pin "23") (pinfunction "23_23") (pintype "passive"))
      (node (ref "DMM_RIGHT") (pin "24") (pinfunction "24_24") (pintype "passive"))
    )
    (net (code "26") (name "/PD0") (class "Default")
      (node (ref "DMM_LEFT") (pin "27") (pinfunction "27_27") (pintype "passive"))
      (node (ref "DMM_LEFT") (pin "28") (pinfunction "28_28") (pintype "passive"))
    )
    (net (code "27") (name "/PD1") (class "Default")
      (node (ref "DMM_LEFT") (pin "29") (pinfunction "29_29") (pintype "passive"))
      (node (ref "DMM_LEFT") (pin "30") (pinfunction "30_30") (pintype "passive"))
    )
    (net (code "28") (name "/REF") (class "Default")
      (node (ref "IC5") (pin "5") (pinfunction "QB_5") (pintype "output"))
      (node (ref "R60") (pin "2") (pinfunction "2_2") (pintype "passive"))
    )
    (net (code "29") (name "/RESET") (class "Default")
      (node (ref "DMM_LEFT") (pin "17") (pinfunction "17_17") (pintype "passive"))
      (node (ref "DMM_LEFT") (pin "18") (pinfunction "18_18") (pintype "passive"))
    )
    (net (code "30") (name "/RX") (class "Default")
      (node (ref "R55") (pin "1") (pinfunction "1_1") (pintype "passive"))
      (node (ref "UART") (pin "1") (pinfunction "1_1") (pintype "passive"))
    )
    (net (code "31") (name "/TX") (class "Default")
      (node (ref "R57") (pin "1") (pinfunction "1_1") (pintype "passive"))
      (node (ref "UART") (pin "3") (pinfunction "3_3") (pintype "passive"))
    )
    (net (code "32") (name "/U_IN") (class "Default")
      (node (ref "K3") (pin "2") (pinfunction "O_2") (pintype "passive"))
      (node (ref "R32") (pin "1") (pinfunction "1_1") (pintype "passive"))
    )
    (net (code "33") (name "/U_I_OUT") (class "Default")
      (node (ref "R19") (pin "1") (pinfunction "1_1") (pintype "passive"))
      (node (ref "R21") (pin "1") (pinfunction "1_1") (pintype "passive"))
      (node (ref "U6") (pin "7") (pinfunction "OUT_7") (pintype "output"))
    )
    (net (code "34") (name "/U_I_RAW") (class "Default")
      (node (ref "K3") (pin "6") (pinfunction "P_6") (pintype "passive"))
      (node (ref "K5") (pin "2") (pinfunction "O_2") (pintype "passive"))
    )
    (net (code "35") (name "/U_I_R_RAW") (class "Default")
      (node (ref "K5") (pin "3") (pinfunction "P_3") (pintype "passive"))
      (node (ref "U5") (pin "3") (pinfunction "IN+_3") (pintype "input"))
    )
    (net (code "36") (name "/U_OUT") (class "Default")
      (node (ref "K2") (pin "6") (pinfunction "P_6") (pintype "passive"))
      (node (ref "K3") (pin "5") (pinfunction "S_5") (pintype "passive"))
    )
    (net (code "37") (name "/XTAL1") (class "Default")
      (node (ref "DMM_LEFT") (pin "25") (pinfunction "25_25") (pintype "passive"))
      (node (ref "DMM_LEFT") (pin "26") (pinfunction "26_26") (pintype "passive"))
    )
    (net (code "38") (name "/XTAL2") (class "Default")
      (node (ref "DMM_LEFT") (pin "23") (pinfunction "23_23") (pintype "passive"))
      (node (ref "DMM_LEFT") (pin "24") (pinfunction "24_24") (pintype "passive"))
    )
    (net (code "39") (name "CNT_IN") (class "Default")
      (node (ref "R13") (pin "1") (pinfunction "1_1") (pintype "passive"))
      (node (ref "SJ1") (pin "2") (pinfunction "2_2") (pintype "passive"))
      (node (ref "U2") (pin "2") (pinfunction "CLK_2") (pintype "input"))
      (node (ref "U3") (pin "5") (pinfunction "Y_5") (pintype "output"))
    )
    (net (code "40") (name "CNT_OUT") (class "Default")
      (node (ref "IC4") (pin "5") (pinfunction "Y_5") (pintype "output"))
      (node (ref "R53") (pin "2") (pinfunction "2_2") (pintype "passive"))
      (node (ref "R54") (pin "2") (pinfunction "2_2") (pintype "passive"))
    )
    (net (code "41") (name "CNT_RES") (class "Default")
      (node (ref "IC6") (pin "15") (pinfunction "QA_15") (pintype "tri_state"))
      (node (ref "U2") (pin "1") (pinfunction "~{CLR}_1") (pintype "input"))
    )
    (net (code "42") (name "DIVSEL1") (class "Default")
      (node (ref "IC4") (pin "11") (pinfunction "A_11") (pintype "input"))
      (node (ref "IC6") (pin "2") (pinfunction "QC_2") (pintype "tri_state"))
    )
    (net (code "43") (name "DIVSEL2") (class "Default")
      (node (ref "IC4") (pin "10") (pinfunction "B_10") (pintype "input"))
      (node (ref "IC6") (pin "3") (pinfunction "QD_3") (pintype "tri_state"))
    )
    (net (code "44") (name "DIVSEL3") (class "Default")
      (node (ref "IC4") (pin "9") (pinfunction "C_9") (pintype "input"))
      (node (ref "IC6") (pin "4") (pinfunction "QE_4") (pintype "tri_state"))
    )
    (net (code "45") (name "GND") (class "Default")
      (node (ref "C10") (pin "2") (pinfunction "2_2") (pintype "passive"))
      (node (ref "C11") (pin "2") (pinfunction "2_2") (pintype "passive"))
      (node (ref "C12") (pin "2") (pinfunction "2_2") (pintype "passive"))
      (node (ref "C13") (pin "2") (pinfunction "2_2") (pintype "passive"))
      (node (ref "C15") (pin "2") (pinfunction "2_2") (pintype "passive"))
      (node (ref "C16") (pin "-") (pinfunction "-_-") (pintype "passive"))
      (node (ref "C18") (pin "2") (pinfunction "2_2") (pintype "passive"))
      (node (ref "C19") (pin "-") (pinfunction "-_-") (pintype "passive"))
      (node (ref "C2") (pin "1") (pinfunction "1_1") (pintype "passive"))
      (node (ref "C20") (pin "-") (pinfunction "-_-") (pintype "passive"))
      (node (ref "C21") (pin "2") (pinfunction "2_2") (pintype "passive"))
      (node (ref "C22") (pin "2") (pinfunction "2_2") (pintype "passive"))
      (node (ref "C23") (pin "-") (pinfunction "-_-") (pintype "passive"))
      (node (ref "C4") (pin "1") (pinfunction "1_1") (pintype "passive"))
      (node (ref "C5") (pin "1") (pinfunction "1_1") (pintype "passive"))
      (node (ref "C6") (pin "1") (pinfunction "1_1") (pintype "passive"))
      (node (ref "C7") (pin "2") (pinfunction "2_2") (pintype "passive"))
      (node (ref "C8") (pin "2") (pinfunction "2_2") (pintype "passive"))
      (node (ref "C9") (pin "2") (pinfunction "2_2") (pintype "passive"))
      (node (ref "D12") (pin "A") (pinfunction "A_A") (pintype "passive"))
      (node (ref "D13") (pin "C") (pinfunction "C_C") (pintype "passive"))
      (node (ref "D2") (pin "A") (pinfunction "A_A") (pintype "passive"))
      (node (ref "D8") (pin "A") (pinfunction "A_A") (pintype "passive"))
      (node (ref "DMM_LEFT") (pin "21") (pinfunction "21_21") (pintype "passive"))
      (node (ref "DMM_LEFT") (pin "22") (pinfunction "22_22") (pintype "passive"))
      (node (ref "DMM_RIGHT") (pin "19") (pinfunction "19_19") (pintype "passive"))
      (node (ref "DMM_RIGHT") (pin "20") (pinfunction "20_20") (pintype "passive"))
      (node (ref "IC1") (pin "1") (pinfunction "I_1") (pintype "input"))
      (node (ref "IC1") (pin "11") (pinfunction "I_11") (pintype "input"))
      (node (ref "IC1") (pin "3") (pinfunction "I_3") (pintype "input"))
      (node (ref "IC1") (pin "5") (pinfunction "I_5") (pintype "input"))
      (node (ref "IC1") (pin "7") (pinfunction "GND_7") (pintype "power_in"))
      (node (ref "IC1") (pin "9") (pinfunction "I_9") (pintype "input"))
      (node (ref "IC2") (pin "1") (pinfunction "GND_1") (pintype "power_in"))
      (node (ref "IC3") (pin "7") (pinfunction "GND_7") (pintype "power_in"))
      (node (ref "IC4") (pin "12") (pinfunction "D7_12") (pintype "input"))
      (node (ref "IC4") (pin "7") (pinfunction "G_7") (pintype "input"))
      (node (ref "IC4") (pin "8") (pinfunction "GND_8") (pintype "power_in"))
      (node (ref "IC5") (pin "1") (pinfunction "A_1") (pintype "input"))
      (node (ref "IC5") (pin "12") (pinfunction "B_12") (pintype "input"))
      (node (ref "IC5") (pin "14") (pinfunction "CLR_14") (pintype "input"))
      (node (ref "IC5") (pin "15") (pinfunction "A_15") (pintype "input"))
      (node (ref "IC5") (pin "2") (pinfunction "CLR_2") (pintype "input"))
      (node (ref "IC5") (pin "8") (pinfunction "GND_8") (pintype "power_in"))
      (node (ref "IC6") (pin "13") (pinfunction "G_13") (pintype "input"))
      (node (ref "IC6") (pin "8") (pinfunction "GND_8") (pintype "power_in"))
      (node (ref "IC7") (pin "13") (pinfunction "G_13") (pintype "input"))
      (node (ref "IC7") (pin "8") (pinfunction "GND_8") (pintype "power_in"))
      (node (ref "IN_LF") (pin "2") (pinfunction "2_2") (pintype "passive"))
      (node (ref "J1") (pin "1@1") (pinfunction "1_1@1") (pintype "bidirectional"))
      (node (ref "J1") (pin "1@2") (pinfunction "2_1@2") (pintype "bidirectional"))
      (node (ref "PCB1") (pin "GND1") (pinfunction "GND1_GND1") (pintype "bidirectional"))
      (node (ref "PCB1") (pin "GND2") (pinfunction "GND2_GND2") (pintype "bidirectional"))
      (node (ref "PCB1") (pin "GND3") (pinfunction "GND3_GND3") (pintype "bidirectional"))
      (node (ref "PCB1") (pin "GND4") (pinfunction "GND4_GND4") (pintype "bidirectional"))
      (node (ref "R10") (pin "2") (pinfunction "2_2") (pintype "passive"))
      (node (ref "R16") (pin "1") (pinfunction "1_1") (pintype "passive"))
      (node (ref "R2") (pin "1") (pinfunction "1_1") (pintype "passive"))
      (node (ref "R20") (pin "2") (pinfunction "2_2") (pintype "passive"))
      (node (ref "R28") (pin "2") (pinfunction "2_2") (pintype "passive"))
      (node (ref "R4") (pin "3") (pinfunction "A_3") (pintype "passive"))
      (node (ref "R6") (pin "1") (pinfunction "1_1") (pintype "passive"))
      (node (ref "R8") (pin "3") (pinfunction "A_3") (pintype "passive"))
      (node (ref "REF10MHZ") (pin "2") (pinfunction "2_2") (pintype "passive"))
      (node (ref "T1") (pin "2") (pinfunction "E_2") (pintype "passive"))
      (node (ref "T10") (pin "2") (pinfunction "E_2") (pintype "passive"))
      (node (ref "T2") (pin "2") (pinfunction "E_2") (pintype "passive"))
      (node (ref "T3") (pin "2") (pinfunction "E_2") (pintype "passive"))
      (node (ref "T4") (pin "2") (pinfunction "E_2") (pintype "passive"))
      (node (ref "U1") (pin "15") (pinfunction "IN+_15") (pintype "bidirectional"))
      (node (ref "U1") (pin "16") (pinfunction "IN-_16") (pintype "bidirectional"))
      (node (ref "U1") (pin "3") (pinfunction "GND_3") (pintype "bidirectional"))
      (node (ref "U1") (pin "6") (pinfunction "VEE_6") (pintype "bidirectional"))
      (node (ref "U1") (pin "7") (pinfunction "IN+_7") (pintype "bidirectional"))
      (node (ref "U1") (pin "8") (pinfunction "IN-_8") (pintype "bidirectional"))
      (node (ref "U2") (pin "3") (pinfunction "A_3") (pintype "input"))
      (node (ref "U2") (pin "4") (pinfunction "B_4") (pintype "input"))
      (node (ref "U2") (pin "5") (pinfunction "C_5") (pintype "input"))
      (node (ref "U2") (pin "6") (pinfunction "D_6") (pintype "input"))
      (node (ref "U2") (pin "8") (pinfunction "GND_8") (pintype "power_in"))
      (node (ref "U3") (pin "4") (pinfunction "GND_4") (pintype "passive"))
      (node (ref "U3") (pin "7") (pinfunction "~{G}_7") (pintype "input"))
      (node (ref "U4") (pin "4") (pinfunction "GND_4") (pintype "bidirectional"))
      (node (ref "U6") (pin "3") (pinfunction "IN+_3") (pintype "input"))
      (node (ref "U6") (pin "4") (pinfunction "VEE_4") (pintype "bidirectional"))
      (node (ref "UART") (pin "2") (pinfunction "2_2") (pintype "passive"))
    )
    (net (code "46") (name "HF") (class "Default")
      (node (ref "PCB1") (pin "OUT") (pinfunction "OUT_OUT") (pintype "bidirectional"))
      (node (ref "U3") (pin "2") (pinfunction "B_2") (pintype "input"))
    )
    (net (code "47") (name "HFSEL1") (class "Default")
      (node (ref "IC6") (pin "6") (pinfunction "QG_6") (pintype "tri_state"))
      (node (ref "PCB1") (pin "DIVSEL1") (pinfunction "DIVSEL1_DIVSEL1") (pintype "bidirectional"))
    )
    (net (code "48") (name "HFSEL2") (class "Default")
      (node (ref "IC6") (pin "5") (pinfunction "QF_5") (pintype "tri_state"))
      (node (ref "PCB1") (pin "DIVSEL2") (pinfunction "DIVSEL2_DIVSEL2") (pintype "bidirectional"))
    )
    (net (code "49") (name "INPUTSEL") (class "Default")
      (node (ref "IC6") (pin "1") (pinfunction "QB_1") (pintype "tri_state"))
      (node (ref "U3") (pin "6") (pinfunction "~{A/B}_6") (pintype "input"))
    )
    (net (code "50") (name "I_10A") (class "Default")
      (node (ref "J3") (pin "1@1") (pinfunction "1_1@1") (pintype "bidirectional"))
      (node (ref "J3") (pin "1@2") (pinfunction "2_1@2") (pintype "bidirectional"))
      (node (ref "R16") (pin "2") (pinfunction "2_2") (pintype "passive"))
      (node (ref "R24") (pin "2") (pinfunction "2_2") (pintype "passive"))
    )
    (net (code "51") (name "I_U{slash}I{slash}R") (class "Default")
      (node (ref "F2") (pin "2A") (pinfunction "2A_2A") (pintype "passive"))
      (node (ref "F2") (pin "2B") (pinfunction "2B_2B") (pintype "passive"))
      (node (ref "J2") (pin "1@1") (pinfunction "1_1@1") (pintype "bidirectional"))
      (node (ref "J2") (pin "1@2") (pinfunction "2_1@2") (pintype "bidirectional"))
    )
    (net (code "52") (name "LF") (class "Default")
      (node (ref "IC3") (pin "12") (pinfunction "D_12") (pintype "input"))
      (node (ref "IC3") (pin "8") (pinfunction "~{Q}_8") (pintype "output"))
      (node (ref "SJ1") (pin "1") (pinfunction "1_1") (pintype "passive"))
      (node (ref "U3") (pin "1") (pinfunction "A_1") (pintype "input"))
    )
    (net (code "53") (name "LF_DIRECT") (class "Default")
      (node (ref "IC4") (pin "14") (pinfunction "D5_14") (pintype "input"))
      (node (ref "R12") (pin "1") (pinfunction "1_1") (pintype "passive"))
    )
    (net (code "54") (name "Net-(C1-Pad1)") (class "Default")
      (node (ref "C1") (pin "1") (pinfunction "1_1") (pintype "passive"))
      (node (ref "IN_LF") (pin "1") (pinfunction "1_1") (pintype "passive"))
    )
    (net (code "55") (name "Net-(C1-Pad2)") (class "Default")
      (node (ref "C1") (pin "2") (pinfunction "2_2") (pintype "passive"))
      (node (ref "R1") (pin "1") (pinfunction "1_1") (pintype "passive"))
      (node (ref "R2") (pin "2") (pinfunction "2_2") (pintype "passive"))
      (node (ref "R3") (pin "2") (pinfunction "2_2") (pintype "passive"))
    )
    (net (code "56") (name "Net-(C3-Pad1)") (class "Default")
      (node (ref "C3") (pin "1") (pinfunction "1_1") (pintype "passive"))
      (node (ref "REF10MHZ") (pin "1") (pinfunction "1_1") (pintype "passive"))
    )
    (net (code "57") (name "Net-(C3-Pad2)") (class "Default")
      (node (ref "C3") (pin "2") (pinfunction "2_2") (pintype "passive"))
      (node (ref "R5") (pin "1") (pinfunction "1_1") (pintype "passive"))
      (node (ref "R6") (pin "2") (pinfunction "2_2") (pintype "passive"))
      (node (ref "R7") (pin "2") (pinfunction "2_2") (pintype "passive"))
    )
    (net (code "58") (name "Net-(C5-Pad2)") (class "Default")
      (node (ref "C5") (pin "2") (pinfunction "2_2") (pintype "passive"))
      (node (ref "D1") (pin "A") (pinfunction "A_A") (pintype "passive"))
      (node (ref "D2") (pin "C") (pinfunction "C_C") (pintype "passive"))
      (node (ref "R10") (pin "1") (pinfunction "1_1") (pintype "passive"))
      (node (ref "R11") (pin "2") (pinfunction "2_2") (pintype "passive"))
      (node (ref "R9") (pin "1") (pinfunction "1_1") (pintype "passive"))
    )
    (net (code "59") (name "Net-(D3-PadC)") (class "Default")
      (node (ref "D3") (pin "C") (pinfunction "C_C") (pintype "passive"))
      (node (ref "D4") (pin "A") (pinfunction "A_A") (pintype "passive"))
    )
    (net (code "60") (name "Net-(IC1A-I)") (class "Default")
      (node (ref "IC1") (pin "13") (pinfunction "I_13") (pintype "input"))
      (node (ref "R11") (pin "1") (pinfunction "1_1") (pintype "passive"))
    )
    (net (code "61") (name "Net-(IC3A-CLK)") (class "Default")
      (node (ref "IC3") (pin "3") (pinfunction "CLK_3") (pintype "input"))
      (node (ref "R12") (pin "2") (pinfunction "2_2") (pintype "passive"))
      (node (ref "U1") (pin "4") (pinfunction "OUT_4") (pintype "bidirectional"))
    )
    (net (code "62") (name "Net-(IC3A-D)") (class "Default")
      (node (ref "IC3") (pin "11") (pinfunction "CLK_11") (pintype "input"))
      (node (ref "IC3") (pin "2") (pinfunction "D_2") (pintype "input"))
      (node (ref "IC3") (pin "6") (pinfunction "~{Q}_6") (pintype "output"))
    )
    (net (code "63") (name "Net-(IC4A-D0)") (class "Default")
      (node (ref "IC4") (pin "4") (pinfunction "D0_4") (pintype "input"))
      (node (ref "U2") (pin "11") (pinfunction "QD_11") (pintype "output"))
    )
    (net (code "64") (name "Net-(IC4A-D1)") (class "Default")
      (node (ref "IC4") (pin "3") (pinfunction "D1_3") (pintype "input"))
      (node (ref "U2") (pin "12") (pinfunction "QC_12") (pintype "output"))
    )
    (net (code "65") (name "Net-(IC4A-D2)") (class "Default")
      (node (ref "IC4") (pin "2") (pinfunction "D2_2") (pintype "input"))
      (node (ref "U2") (pin "13") (pinfunction "QB_13") (pintype "output"))
    )
    (net (code "66") (name "Net-(IC4A-D3)") (class "Default")
      (node (ref "IC4") (pin "1") (pinfunction "D3_1") (pintype "input"))
      (node (ref "U2") (pin "14") (pinfunction "QA_14") (pintype "output"))
    )
    (net (code "67") (name "Net-(IC4A-D4)") (class "Default")
      (node (ref "IC4") (pin "15") (pinfunction "D4_15") (pintype "input"))
      (node (ref "R13") (pin "2") (pinfunction "2_2") (pintype "passive"))
    )
    (net (code "68") (name "Net-(IC5A-B)") (class "Default")
      (node (ref "IC5") (pin "4") (pinfunction "B_4") (pintype "input"))
      (node (ref "U1") (pin "12") (pinfunction "OUT_12") (pintype "bidirectional"))
    )
    (net (code "69") (name "Net-(IC6A-QH*)") (class "Default")
      (node (ref "IC6") (pin "9") (pinfunction "QH*_9") (pintype "tri_state"))
      (node (ref "IC7") (pin "14") (pinfunction "SER_14") (pintype "input"))
    )
    (net (code "70") (name "Net-(J4-1)") (class "Default")
      (node (ref "J4") (pin "1@1") (pinfunction "1_1@1") (pintype "bidirectional"))
      (node (ref "J4") (pin "1@2") (pinfunction "2_1@2") (pintype "bidirectional"))
      (node (ref "R9") (pin "2") (pinfunction "2_2") (pintype "passive"))
    )
    (net (code "71") (name "Net-(K1A--)") (class "Default")
      (node (ref "D11") (pin "A") (pinfunction "A_A") (pintype "passive"))
      (node (ref "D5") (pin "A") (pinfunction "A_A") (pintype "passive"))
      (node (ref "K1") (pin "8") (pinfunction "-_8") (pintype "passive"))
      (node (ref "K4") (pin "8") (pinfunction "-_8") (pintype "passive"))
      (node (ref "T3") (pin "3") (pinfunction "C_3") (pintype "passive"))
    )
    (net (code "72") (name "Net-(K1B-O)") (class "Default")
      (node (ref "K1") (pin "2") (pinfunction "O_2") (pintype "passive"))
      (node (ref "R26") (pin "1") (pinfunction "1_1") (pintype "passive"))
      (node (ref "R27") (pin "2") (pinfunction "2_2") (pintype "passive"))
    )
    (net (code "73") (name "Net-(K1B-P)") (class "Default")
      (node (ref "K1") (pin "3") (pinfunction "P_3") (pintype "passive"))
      (node (ref "K2") (pin "4") (pinfunction "S_4") (pintype "passive"))
    )
    (net (code "74") (name "Net-(K1C-O)") (class "Default")
      (node (ref "K1") (pin "7") (pinfunction "O_7") (pintype "passive"))
      (node (ref "R24") (pin "1") (pinfunction "1_1") (pintype "passive"))
      (node (ref "R25") (pin "2") (pinfunction "2_2") (pintype "passive"))
    )
    (net (code "75") (name "Net-(K1C-P)") (class "Default")
      (node (ref "K1") (pin "6") (pinfunction "P_6") (pintype "passive"))
      (node (ref "K2") (pin "2") (pinfunction "O_2") (pintype "passive"))
    )
    (net (code "76") (name "Net-(K1C-S)") (class "Default")
      (node (ref "K1") (pin "5") (pinfunction "S_5") (pintype "passive"))
      (node (ref "R25") (pin "1") (pinfunction "1_1") (pintype "passive"))
      (node (ref "R26") (pin "2") (pinfunction "2_2") (pintype "passive"))
    )
    (net (code "77") (name "Net-(K2A--)") (class "Default")
      (node (ref "D6") (pin "A") (pinfunction "A_A") (pintype "passive"))
      (node (ref "K2") (pin "8") (pinfunction "-_8") (pintype "passive"))
      (node (ref "T2") (pin "3") (pinfunction "C_3") (pintype "passive"))
    )
    (net (code "78") (name "Net-(K2C-O)") (class "Default")
      (node (ref "K2") (pin "7") (pinfunction "O_7") (pintype "passive"))
      (node (ref "K4") (pin "6") (pinfunction "P_6") (pintype "passive"))
    )
    (net (code "79") (name "Net-(K2C-S)") (class "Default")
      (node (ref "K2") (pin "5") (pinfunction "S_5") (pintype "passive"))
      (node (ref "K4") (pin "3") (pinfunction "P_3") (pintype "passive"))
    )
    (net (code "80") (name "Net-(K3A--)") (class "Default")
      (node (ref "D7") (pin "A") (pinfunction "A_A") (pintype "passive"))
      (node (ref "K3") (pin "8") (pinfunction "-_8") (pintype "passive"))
      (node (ref "T4") (pin "3") (pinfunction "C_3") (pintype "passive"))
    )
    (net (code "81") (name "Net-(K3B-P)") (class "Default")
      (node (ref "K3") (pin "3") (pinfunction "P_3") (pintype "passive"))
      (node (ref "K5") (pin "7") (pinfunction "O_7") (pintype "passive"))
    )
    (net (code "82") (name "Net-(K4B-O)") (class "Default")
      (node (ref "K4") (pin "2") (pinfunction "O_2") (pintype "passive"))
      (node (ref "R30") (pin "1") (pinfunction "1_1") (pintype "passive"))
      (node (ref "R31") (pin "2") (pinfunction "2_2") (pintype "passive"))
    )
    (net (code "83") (name "Net-(K4B-S)") (class "Default")
      (node (ref "K4") (pin "4") (pinfunction "S_4") (pintype "passive"))
      (node (ref "R31") (pin "1") (pinfunction "1_1") (pintype "passive"))
      (node (ref "R32") (pin "2") (pinfunction "2_2") (pintype "passive"))
    )
    (net (code "84") (name "Net-(K4C-O)") (class "Default")
      (node (ref "K4") (pin "7") (pinfunction "O_7") (pintype "passive"))
      (node (ref "R28") (pin "1") (pinfunction "1_1") (pintype "passive"))
      (node (ref "R29") (pin "2") (pinfunction "2_2") (pintype "passive"))
    )
    (net (code "85") (name "Net-(K4C-S)") (class "Default")
      (node (ref "K4") (pin "5") (pinfunction "S_5") (pintype "passive"))
      (node (ref "R29") (pin "1") (pinfunction "1_1") (pintype "passive"))
      (node (ref "R30") (pin "2") (pinfunction "2_2") (pintype "passive"))
    )
    (net (code "86") (name "Net-(K5A--)") (class "Default")
      (node (ref "D10") (pin "A") (pinfunction "A_A") (pintype "passive"))
      (node (ref "K5") (pin "8") (pinfunction "-_8") (pintype "passive"))
      (node (ref "T10") (pin "3") (pinfunction "C_3") (pintype "passive"))
    )
    (net (code "87") (name "Net-(K5B-S)") (class "Default")
      (node (ref "K5") (pin "4") (pinfunction "S_4") (pintype "passive"))
      (node (ref "K5") (pin "5") (pinfunction "S_5") (pintype "passive"))
      (node (ref "R37") (pin "1") (pinfunction "1_1") (pintype "passive"))
      (node (ref "R40") (pin "1") (pinfunction "1_1") (pintype "passive"))
      (node (ref "R43") (pin "1") (pinfunction "1_1") (pintype "passive"))
      (node (ref "R46") (pin "1") (pinfunction "1_1") (pintype "passive"))
      (node (ref "R49") (pin "1") (pinfunction "1_1") (pintype "passive"))
    )
    (net (code "88") (name "Net-(K5C-P)") (class "Default")
      (node (ref "F2") (pin "1A") (pinfunction "1A_1A") (pintype "passive"))
      (node (ref "F2") (pin "1B") (pinfunction "1B_1B") (pintype "passive"))
      (node (ref "K5") (pin "6") (pinfunction "P_6") (pintype "passive"))
    )
    (net (code "89") (name "Net-(R4-S)") (class "Default")
      (node (ref "C2") (pin "2") (pinfunction "2_2") (pintype "passive"))
      (node (ref "R4") (pin "2") (pinfunction "S_2") (pintype "passive"))
      (node (ref "U1") (pin "1") (pinfunction "IN-_1") (pintype "bidirectional"))
    )
    (net (code "90") (name "Net-(R8-S)") (class "Default")
      (node (ref "C4") (pin "2") (pinfunction "2_2") (pintype "passive"))
      (node (ref "R8") (pin "2") (pinfunction "S_2") (pintype "passive"))
      (node (ref "U1") (pin "9") (pinfunction "IN-_9") (pintype "bidirectional"))
    )
    (net (code "91") (name "Net-(R36-Pad2)") (class "Default")
      (node (ref "R36") (pin "2") (pinfunction "2_2") (pintype "passive"))
      (node (ref "R38") (pin "1") (pinfunction "1_1") (pintype "passive"))
      (node (ref "T5") (pin "B") (pinfunction "B_B") (pintype "passive"))
    )
    (net (code "92") (name "Net-(R37-Pad2)") (class "Default")
      (node (ref "R37") (pin "2") (pinfunction "2_2") (pintype "passive"))
      (node (ref "T5") (pin "C") (pinfunction "C_C") (pintype "passive"))
    )
    (net (code "93") (name "Net-(R39-Pad2)") (class "Default")
      (node (ref "R39") (pin "2") (pinfunction "2_2") (pintype "passive"))
      (node (ref "R41") (pin "1") (pinfunction "1_1") (pintype "passive"))
      (node (ref "T6") (pin "B") (pinfunction "B_B") (pintype "passive"))
    )
    (net (code "94") (name "Net-(R40-Pad2)") (class "Default")
      (node (ref "R40") (pin "2") (pinfunction "2_2") (pintype "passive"))
      (node (ref "T6") (pin "C") (pinfunction "C_C") (pintype "passive"))
    )
    (net (code "95") (name "Net-(R42-Pad2)") (class "Default")
      (node (ref "R42") (pin "2") (pinfunction "2_2") (pintype "passive"))
      (node (ref "R44") (pin "1") (pinfunction "1_1") (pintype "passive"))
      (node (ref "T7") (pin "B") (pinfunction "B_B") (pintype "passive"))
    )
    (net (code "96") (name "Net-(R43-Pad2)") (class "Default")
      (node (ref "R43") (pin "2") (pinfunction "2_2") (pintype "passive"))
      (node (ref "T7") (pin "C") (pinfunction "C_C") (pintype "passive"))
    )
    (net (code "97") (name "Net-(R45-Pad2)") (class "Default")
      (node (ref "R45") (pin "2") (pinfunction "2_2") (pintype "passive"))
      (node (ref "R47") (pin "1") (pinfunction "1_1") (pintype "passive"))
      (node (ref "T8") (pin "B") (pinfunction "B_B") (pintype "passive"))
    )
    (net (code "98") (name "Net-(R46-Pad2)") (class "Default")
      (node (ref "R46") (pin "2") (pinfunction "2_2") (pintype "passive"))
      (node (ref "T8") (pin "C") (pinfunction "C_C") (pintype "passive"))
    )
    (net (code "99") (name "Net-(R48-Pad2)") (class "Default")
      (node (ref "R48") (pin "2") (pinfunction "2_2") (pintype "passive"))
      (node (ref "R50") (pin "1") (pinfunction "1_1") (pintype "passive"))
      (node (ref "T9") (pin "B") (pinfunction "B_B") (pintype "passive"))
    )
    (net (code "100") (name "Net-(R49-Pad2)") (class "Default")
      (node (ref "R49") (pin "2") (pinfunction "2_2") (pintype "passive"))
      (node (ref "T9") (pin "C") (pinfunction "C_C") (pintype "passive"))
    )
    (net (code "101") (name "Net-(T1-B)") (class "Default")
      (node (ref "R22") (pin "2") (pinfunction "2_2") (pintype "passive"))
      (node (ref "T1") (pin "1") (pinfunction "B_1") (pintype "passive"))
    )
    (net (code "102") (name "Net-(T2-B)") (class "Default")
      (node (ref "R33") (pin "2") (pinfunction "2_2") (pintype "passive"))
      (node (ref "T2") (pin "1") (pinfunction "B_1") (pintype "passive"))
    )
    (net (code "103") (name "Net-(T3-B)") (class "Default")
      (node (ref "R34") (pin "2") (pinfunction "2_2") (pintype "passive"))
      (node (ref "T3") (pin "1") (pinfunction "B_1") (pintype "passive"))
    )
    (net (code "104") (name "Net-(T4-B)") (class "Default")
      (node (ref "R35") (pin "2") (pinfunction "2_2") (pintype "passive"))
      (node (ref "T4") (pin "1") (pinfunction "B_1") (pintype "passive"))
    )
    (net (code "105") (name "Net-(T10-B)") (class "Default")
      (node (ref "R52") (pin "2") (pinfunction "2_2") (pintype "passive"))
      (node (ref "T10") (pin "1") (pinfunction "B_1") (pintype "passive"))
    )
    (net (code "106") (name "Net-(U1A-IN+)") (class "Default")
      (node (ref "R3") (pin "1") (pinfunction "1_1") (pintype "passive"))
      (node (ref "U1") (pin "2") (pinfunction "IN+_2") (pintype "bidirectional"))
    )
    (net (code "107") (name "Net-(U1C-IN+)") (class "Default")
      (node (ref "R7") (pin "1") (pinfunction "1_1") (pintype "passive"))
      (node (ref "U1") (pin "10") (pinfunction "IN+_10") (pintype "bidirectional"))
    )
    (net (code "108") (name "Net-(U4-C1+)") (class "Default")
      (node (ref "C14") (pin "2") (pinfunction "2_2") (pintype "passive"))
      (node (ref "U4") (pin "5") (pinfunction "C1+_5") (pintype "bidirectional"))
    )
    (net (code "109") (name "Net-(U4-C1-)") (class "Default")
      (node (ref "C14") (pin "1") (pinfunction "1_1") (pintype "passive"))
      (node (ref "U4") (pin "3") (pinfunction "C1-_3") (pintype "bidirectional"))
    )
    (net (code "110") (name "Net-(U5A-IN-)") (class "Default")
      (node (ref "R17") (pin "2") (pinfunction "2_2") (pintype "passive"))
      (node (ref "R51") (pin "2") (pinfunction "2_2") (pintype "passive"))
      (node (ref "U5") (pin "2") (pinfunction "IN-_2") (pintype "input"))
      (node (ref "U5") (pin "6") (pinfunction "OUT_6") (pintype "output"))
    )
    (net (code "111") (name "Net-(U6A-IN-)") (class "Default")
      (node (ref "R17") (pin "1") (pinfunction "1_1") (pintype "passive"))
      (node (ref "R18") (pin "2") (pinfunction "2_2") (pintype "passive"))
      (node (ref "U6") (pin "2") (pinfunction "IN-_2") (pintype "input"))
    )
    (net (code "112") (name "Net-(U6A-OUT)") (class "Default")
      (node (ref "D3") (pin "A") (pinfunction "A_A") (pintype "passive"))
      (node (ref "R22") (pin "1") (pinfunction "1_1") (pintype "passive"))
      (node (ref "U6") (pin "1") (pinfunction "OUT_1") (pintype "output"))
    )
    (net (code "113") (name "Net-(U6B-IN+)") (class "Default")
      (node (ref "D4") (pin "C") (pinfunction "C_C") (pintype "passive"))
      (node (ref "R18") (pin "1") (pinfunction "1_1") (pintype "passive"))
      (node (ref "U6") (pin "5") (pinfunction "IN+_5") (pintype "input"))
    )
    (net (code "114") (name "Net-(U6B-IN-)") (class "Default")
      (node (ref "R19") (pin "2") (pinfunction "2_2") (pintype "passive"))
      (node (ref "R20") (pin "1") (pinfunction "1_1") (pintype "passive"))
      (node (ref "U6") (pin "6") (pinfunction "IN-_6") (pintype "input"))
    )
    (net (code "115") (name "PA0") (class "Default")
      (node (ref "C16") (pin "+") (pinfunction "+_+") (pintype "passive"))
      (node (ref "DMM_RIGHT") (pin "2") (pinfunction "2_2") (pintype "passive"))
      (node (ref "R21") (pin "2") (pinfunction "2_2") (pintype "passive"))
    )
    (net (code "116") (name "PA1") (class "Default")
      (node (ref "C23") (pin "+") (pinfunction "+_+") (pintype "passive"))
      (node (ref "D8") (pin "C") (pinfunction "C_C") (pintype "passive"))
      (node (ref "D9") (pin "A") (pinfunction "A_A") (pintype "passive"))
      (node (ref "DMM_RIGHT") (pin "4") (pinfunction "4_4") (pintype "passive"))
      (node (ref "R51") (pin "1") (pinfunction "1_1") (pintype "passive"))
    )
    (net (code "117") (name "PA2") (class "Default")
      (node (ref "DMM_RIGHT") (pin "6") (pinfunction "6_6") (pintype "passive"))
      (node (ref "IC6") (pin "14") (pinfunction "SER_14") (pintype "input"))
    )
    (net (code "118") (name "PB0") (class "Default")
      (node (ref "DMM_LEFT") (pin "1") (pinfunction "1_1") (pintype "passive"))
      (node (ref "R53") (pin "1") (pinfunction "1_1") (pintype "passive"))
    )
    (net (code "119") (name "PB1") (class "Default")
      (node (ref "DMM_LEFT") (pin "3") (pinfunction "3_3") (pintype "passive"))
      (node (ref "R60") (pin "1") (pinfunction "1_1") (pintype "passive"))
    )
    (net (code "120") (name "PB2") (class "Default")
      (node (ref "DMM_LEFT") (pin "5") (pinfunction "5_5") (pintype "passive"))
      (node (ref "R23") (pin "2") (pinfunction "2_2") (pintype "passive"))
      (node (ref "T1") (pin "3") (pinfunction "C_3") (pintype "passive"))
    )
    (net (code "121") (name "PD2") (class "Default")
      (node (ref "DMM_LEFT") (pin "31") (pinfunction "31_31") (pintype "passive"))
      (node (ref "R55") (pin "2") (pinfunction "2_2") (pintype "passive"))
    )
    (net (code "122") (name "PD3") (class "Default")
      (node (ref "DMM_LEFT") (pin "33") (pinfunction "33_33") (pintype "passive"))
      (node (ref "R57") (pin "2") (pinfunction "2_2") (pintype "passive"))
    )
    (net (code "123") (name "PD4") (class "Default")
      (node (ref "DMM_LEFT") (pin "35") (pinfunction "35_35") (pintype "passive"))
      (node (ref "R56") (pin "2") (pinfunction "2_2") (pintype "passive"))
    )
    (net (code "124") (name "PD5") (class "Default")
      (node (ref "DMM_LEFT") (pin "37") (pinfunction "37_37") (pintype "passive"))
      (node (ref "IC6") (pin "12") (pinfunction "RCK_12") (pintype "input"))
      (node (ref "IC7") (pin "12") (pinfunction "RCK_12") (pintype "input"))
    )
    (net (code "125") (name "PD6") (class "Default")
      (node (ref "DMM_LEFT") (pin "39") (pinfunction "39_39") (pintype "passive"))
      (node (ref "R54") (pin "1") (pinfunction "1_1") (pintype "passive"))
    )
    (net (code "126") (name "PD7") (class "Default")
      (node (ref "DMM_RIGHT") (pin "40") (pinfunction "40_40") (pintype "passive"))
      (node (ref "IC6") (pin "11") (pinfunction "SCK_11") (pintype "input"))
      (node (ref "IC7") (pin "11") (pinfunction "SCK_11") (pintype "input"))
    )
    (net (code "127") (name "RANGE_LSB") (class "Default")
      (node (ref "IC6") (pin "7") (pinfunction "QH_7") (pintype "tri_state"))
      (node (ref "R34") (pin "1") (pinfunction "1_1") (pintype "passive"))
    )
    (net (code "128") (name "RANGE_MSB") (class "Default")
      (node (ref "IC7") (pin "15") (pinfunction "QA_15") (pintype "tri_state"))
      (node (ref "R33") (pin "1") (pinfunction "1_1") (pintype "passive"))
    )
    (net (code "129") (name "R_RANGE1") (class "Default")
      (node (ref "IC7") (pin "5") (pinfunction "QF_5") (pintype "tri_state"))
      (node (ref "R36") (pin "1") (pinfunction "1_1") (pintype "passive"))
    )
    (net (code "130") (name "R_RANGE2") (class "Default")
      (node (ref "IC7") (pin "4") (pinfunction "QE_4") (pintype "tri_state"))
      (node (ref "R39") (pin "1") (pinfunction "1_1") (pintype "passive"))
    )
    (net (code "131") (name "R_RANGE3") (class "Default")
      (node (ref "IC7") (pin "3") (pinfunction "QD_3") (pintype "tri_state"))
      (node (ref "R42") (pin "1") (pinfunction "1_1") (pintype "passive"))
    )
    (net (code "132") (name "R_RANGE4") (class "Default")
      (node (ref "IC7") (pin "2") (pinfunction "QC_2") (pintype "tri_state"))
      (node (ref "R45") (pin "1") (pinfunction "1_1") (pintype "passive"))
    )
    (net (code "133") (name "R_RANGE5") (class "Default")
      (node (ref "IC7") (pin "1") (pinfunction "QB_1") (pintype "tri_state"))
      (node (ref "R48") (pin "1") (pinfunction "1_1") (pintype "passive"))
    )
    (net (code "134") (name "R_SELECTOR") (class "Default")
      (node (ref "IC7") (pin "7") (pinfunction "QH_7") (pintype "tri_state"))
      (node (ref "R52") (pin "1") (pinfunction "1_1") (pintype "passive"))
    )
    (net (code "135") (name "TTL") (class "Default")
      (node (ref "IC1") (pin "12") (pinfunction "O_12") (pintype "output"))
      (node (ref "IC4") (pin "13") (pinfunction "D6_13") (pintype "input"))
    )
    (net (code "136") (name "U_I_SELECTOR") (class "Default")
      (node (ref "IC7") (pin "6") (pinfunction "QG_6") (pintype "tri_state"))
      (node (ref "R35") (pin "1") (pinfunction "1_1") (pintype "passive"))
    )
    (net (code "137") (name "VCC") (class "Default")
      (node (ref "C10") (pin "1") (pinfunction "1_1") (pintype "passive"))
      (node (ref "C11") (pin "1") (pinfunction "1_1") (pintype "passive"))
      (node (ref "C12") (pin "1") (pinfunction "1_1") (pintype "passive"))
      (node (ref "C13") (pin "1") (pinfunction "1_1") (pintype "passive"))
      (node (ref "C17") (pin "1") (pinfunction "1_1") (pintype "passive"))
      (node (ref "C18") (pin "1") (pinfunction "1_1") (pintype "passive"))
      (node (ref "C20") (pin "+") (pinfunction "+_+") (pintype "passive"))
      (node (ref "C21") (pin "1") (pinfunction "1_1") (pintype "passive"))
      (node (ref "C22") (pin "1") (pinfunction "1_1") (pintype "passive"))
      (node (ref "C6") (pin "2") (pinfunction "2_2") (pintype "passive"))
      (node (ref "C7") (pin "1") (pinfunction "1_1") (pintype "passive"))
      (node (ref "C8") (pin "1") (pinfunction "1_1") (pintype "passive"))
      (node (ref "C9") (pin "1") (pinfunction "1_1") (pintype "passive"))
      (node (ref "D1") (pin "C") (pinfunction "C_C") (pintype "passive"))
      (node (ref "D10") (pin "C") (pinfunction "C_C") (pintype "passive"))
      (node (ref "D11") (pin "C") (pinfunction "C_C") (pintype "passive"))
      (node (ref "D5") (pin "C") (pinfunction "C_C") (pintype "passive"))
      (node (ref "D6") (pin "C") (pinfunction "C_C") (pintype "passive"))
      (node (ref "D7") (pin "C") (pinfunction "C_C") (pintype "passive"))
      (node (ref "D9") (pin "C") (pinfunction "C_C") (pintype "passive"))
      (node (ref "DMM_LEFT") (pin "19") (pinfunction "19_19") (pintype "passive"))
      (node (ref "DMM_LEFT") (pin "20") (pinfunction "20_20") (pintype "passive"))
      (node (ref "IC1") (pin "14") (pinfunction "VCC_14") (pintype "power_in"))
      (node (ref "IC2") (pin "3") (pinfunction "VIN_3") (pintype "input"))
      (node (ref "IC3") (pin "1") (pinfunction "CLR_1") (pintype "input"))
      (node (ref "IC3") (pin "10") (pinfunction "PRE_10") (pintype "input"))
      (node (ref "IC3") (pin "13") (pinfunction "CLR_13") (pintype "input"))
      (node (ref "IC3") (pin "14") (pinfunction "VCC_14") (pintype "power_in"))
      (node (ref "IC3") (pin "4") (pinfunction "PRE_4") (pintype "input"))
      (node (ref "IC4") (pin "16") (pinfunction "VCC_16") (pintype "power_in"))
      (node (ref "IC5") (pin "16") (pinfunction "VCC_16") (pintype "power_in"))
      (node (ref "IC6") (pin "10") (pinfunction "SCL_10") (pintype "input"))
      (node (ref "IC6") (pin "16") (pinfunction "VCC_16") (pintype "power_in"))
      (node (ref "IC7") (pin "10") (pinfunction "SCL_10") (pintype "input"))
      (node (ref "IC7") (pin "16") (pinfunction "VCC_16") (pintype "power_in"))
      (node (ref "K1") (pin "1") (pinfunction "+_1") (pintype "passive"))
      (node (ref "K2") (pin "1") (pinfunction "+_1") (pintype "passive"))
      (node (ref "K3") (pin "1") (pinfunction "+_1") (pintype "passive"))
      (node (ref "K4") (pin "1") (pinfunction "+_1") (pintype "passive"))
      (node (ref "K5") (pin "1") (pinfunction "+_1") (pintype "passive"))
      (node (ref "PCB1") (pin "VCC") (pinfunction "VCC_VCC") (pintype "bidirectional"))
      (node (ref "R1") (pin "2") (pinfunction "2_2") (pintype "passive"))
      (node (ref "R23") (pin "1") (pinfunction "1_1") (pintype "passive"))
      (node (ref "R4") (pin "1") (pinfunction "E_1") (pintype "passive"))
      (node (ref "R5") (pin "2") (pinfunction "2_2") (pintype "passive"))
      (node (ref "R8") (pin "1") (pinfunction "E_1") (pintype "passive"))
      (node (ref "U1") (pin "11") (pinfunction "VDD_11") (pintype "bidirectional"))
      (node (ref "U1") (pin "14") (pinfunction "VCC_14") (pintype "bidirectional"))
      (node (ref "U2") (pin "10") (pinfunction "ENT_10") (pintype "input"))
      (node (ref "U2") (pin "16") (pinfunction "VCC_16") (pintype "power_in"))
      (node (ref "U2") (pin "9") (pinfunction "~{LOAD}_9") (pintype "input"))
      (node (ref "U3") (pin "8") (pinfunction "VCC_8") (pintype "power_in"))
      (node (ref "U4") (pin "2") (pinfunction "V_IN_2") (pintype "bidirectional"))
      (node (ref "U5") (pin "7") (pinfunction "VCC_7") (pintype "bidirectional"))
      (node (ref "U6") (pin "8") (pinfunction "VCC_8") (pintype "bidirectional"))
    )
    (net (code "138") (name "unconnected-(DMM_LEFT-Pad2)") (class "Default")
      (node (ref "DMM_LEFT") (pin "2") (pinfunction "2_2") (pintype "passive"))
    )
    (net (code "139") (name "unconnected-(DMM_LEFT-Pad4)") (class "Default")
      (node (ref "DMM_LEFT") (pin "4") (pinfunction "4_4") (pintype "passive"))
    )
    (net (code "140") (name "unconnected-(DMM_LEFT-Pad6)") (class "Default")
      (node (ref "DMM_LEFT") (pin "6") (pinfunction "6_6") (pintype "passive"))
    )
    (net (code "141") (name "unconnected-(DMM_LEFT-Pad32)") (class "Default")
      (node (ref "DMM_LEFT") (pin "32") (pinfunction "32_32") (pintype "passive"))
    )
    (net (code "142") (name "unconnected-(DMM_LEFT-Pad34)") (class "Default")
      (node (ref "DMM_LEFT") (pin "34") (pinfunction "34_34") (pintype "passive"))
    )
    (net (code "143") (name "unconnected-(DMM_LEFT-Pad36)") (class "Default")
      (node (ref "DMM_LEFT") (pin "36") (pinfunction "36_36") (pintype "passive"))
    )
    (net (code "144") (name "unconnected-(DMM_LEFT-Pad38)") (class "Default")
      (node (ref "DMM_LEFT") (pin "38") (pinfunction "38_38") (pintype "passive"))
    )
    (net (code "145") (name "unconnected-(DMM_LEFT-Pad40)") (class "Default")
      (node (ref "DMM_LEFT") (pin "40") (pinfunction "40_40") (pintype "passive"))
    )
    (net (code "146") (name "unconnected-(DMM_RIGHT-Pad1)") (class "Default")
      (node (ref "DMM_RIGHT") (pin "1") (pinfunction "1_1") (pintype "passive"))
    )
    (net (code "147") (name "unconnected-(DMM_RIGHT-Pad3)") (class "Default")
      (node (ref "DMM_RIGHT") (pin "3") (pinfunction "3_3") (pintype "passive"))
    )
    (net (code "148") (name "unconnected-(DMM_RIGHT-Pad5)") (class "Default")
      (node (ref "DMM_RIGHT") (pin "5") (pinfunction "5_5") (pintype "passive"))
    )
    (net (code "149") (name "unconnected-(DMM_RIGHT-Pad39)") (class "Default")
      (node (ref "DMM_RIGHT") (pin "39") (pinfunction "39_39") (pintype "passive"))
    )
    (net (code "150") (name "unconnected-(IC1B-O-Pad10)") (class "Default")
      (node (ref "IC1") (pin "10") (pinfunction "O_10") (pintype "output"))
    )
    (net (code "151") (name "unconnected-(IC1C-O-Pad8)") (class "Default")
      (node (ref "IC1") (pin "8") (pinfunction "O_8") (pintype "output"))
    )
    (net (code "152") (name "unconnected-(IC1D-O-Pad2)") (class "Default")
      (node (ref "IC1") (pin "2") (pinfunction "O_2") (pintype "output"))
    )
    (net (code "153") (name "unconnected-(IC1E-O-Pad4)") (class "Default")
      (node (ref "IC1") (pin "4") (pinfunction "O_4") (pintype "output"))
    )
    (net (code "154") (name "unconnected-(IC1F-O-Pad6)") (class "Default")
      (node (ref "IC1") (pin "6") (pinfunction "O_6") (pintype "output"))
    )
    (net (code "155") (name "unconnected-(IC3A-Q-Pad5)") (class "Default")
      (node (ref "IC3") (pin "5") (pinfunction "Q_5") (pintype "output"))
    )
    (net (code "156") (name "unconnected-(IC3B-Q-Pad9)") (class "Default")
      (node (ref "IC3") (pin "9") (pinfunction "Q_9") (pintype "output"))
    )
    (net (code "157") (name "unconnected-(IC4A-W-Pad6)") (class "Default")
      (node (ref "IC4") (pin "6") (pinfunction "W_6") (pintype "output"))
    )
    (net (code "158") (name "unconnected-(IC5A-QA-Pad3)") (class "Default")
      (node (ref "IC5") (pin "3") (pinfunction "QA_3") (pintype "output"))
    )
    (net (code "159") (name "unconnected-(IC5A-QC-Pad6)") (class "Default")
      (node (ref "IC5") (pin "6") (pinfunction "QC_6") (pintype "output"))
    )
    (net (code "160") (name "unconnected-(IC5A-QD-Pad7)") (class "Default")
      (node (ref "IC5") (pin "7") (pinfunction "QD_7") (pintype "output"))
    )
    (net (code "161") (name "unconnected-(IC5B-QA-Pad13)") (class "Default")
      (node (ref "IC5") (pin "13") (pinfunction "QA_13") (pintype "output"))
    )
    (net (code "162") (name "unconnected-(IC5B-QB-Pad11)") (class "Default")
      (node (ref "IC5") (pin "11") (pinfunction "QB_11") (pintype "output"))
    )
    (net (code "163") (name "unconnected-(IC5B-QC-Pad10)") (class "Default")
      (node (ref "IC5") (pin "10") (pinfunction "QC_10") (pintype "output"))
    )
    (net (code "164") (name "unconnected-(IC5B-QD-Pad9)") (class "Default")
      (node (ref "IC5") (pin "9") (pinfunction "QD_9") (pintype "output"))
    )
    (net (code "165") (name "unconnected-(IC7A-QH*-Pad9)") (class "Default")
      (node (ref "IC7") (pin "9") (pinfunction "QH*_9") (pintype "tri_state"))
    )
    (net (code "166") (name "unconnected-(U1B-OUT-Pad5)") (class "Default")
      (node (ref "U1") (pin "5") (pinfunction "OUT_5") (pintype "bidirectional"))
    )
    (net (code "167") (name "unconnected-(U1D-OUT-Pad13)") (class "Default")
      (node (ref "U1") (pin "13") (pinfunction "OUT_13") (pintype "bidirectional"))
    )
    (net (code "168") (name "unconnected-(U2A-RCO-Pad15)") (class "Default")
      (node (ref "U2") (pin "15") (pinfunction "RCO_15") (pintype "output"))
    )
    (net (code "169") (name "unconnected-(U3-~{Y}-Pad3)") (class "Default")
      (node (ref "U3") (pin "3") (pinfunction "~{Y}_3") (pintype "output"))
    )
  )
)
